# SCH_LED-bargraph-1_6_2024-11-01.net
KiCad netlist of a schematic drawn in EasyEDA
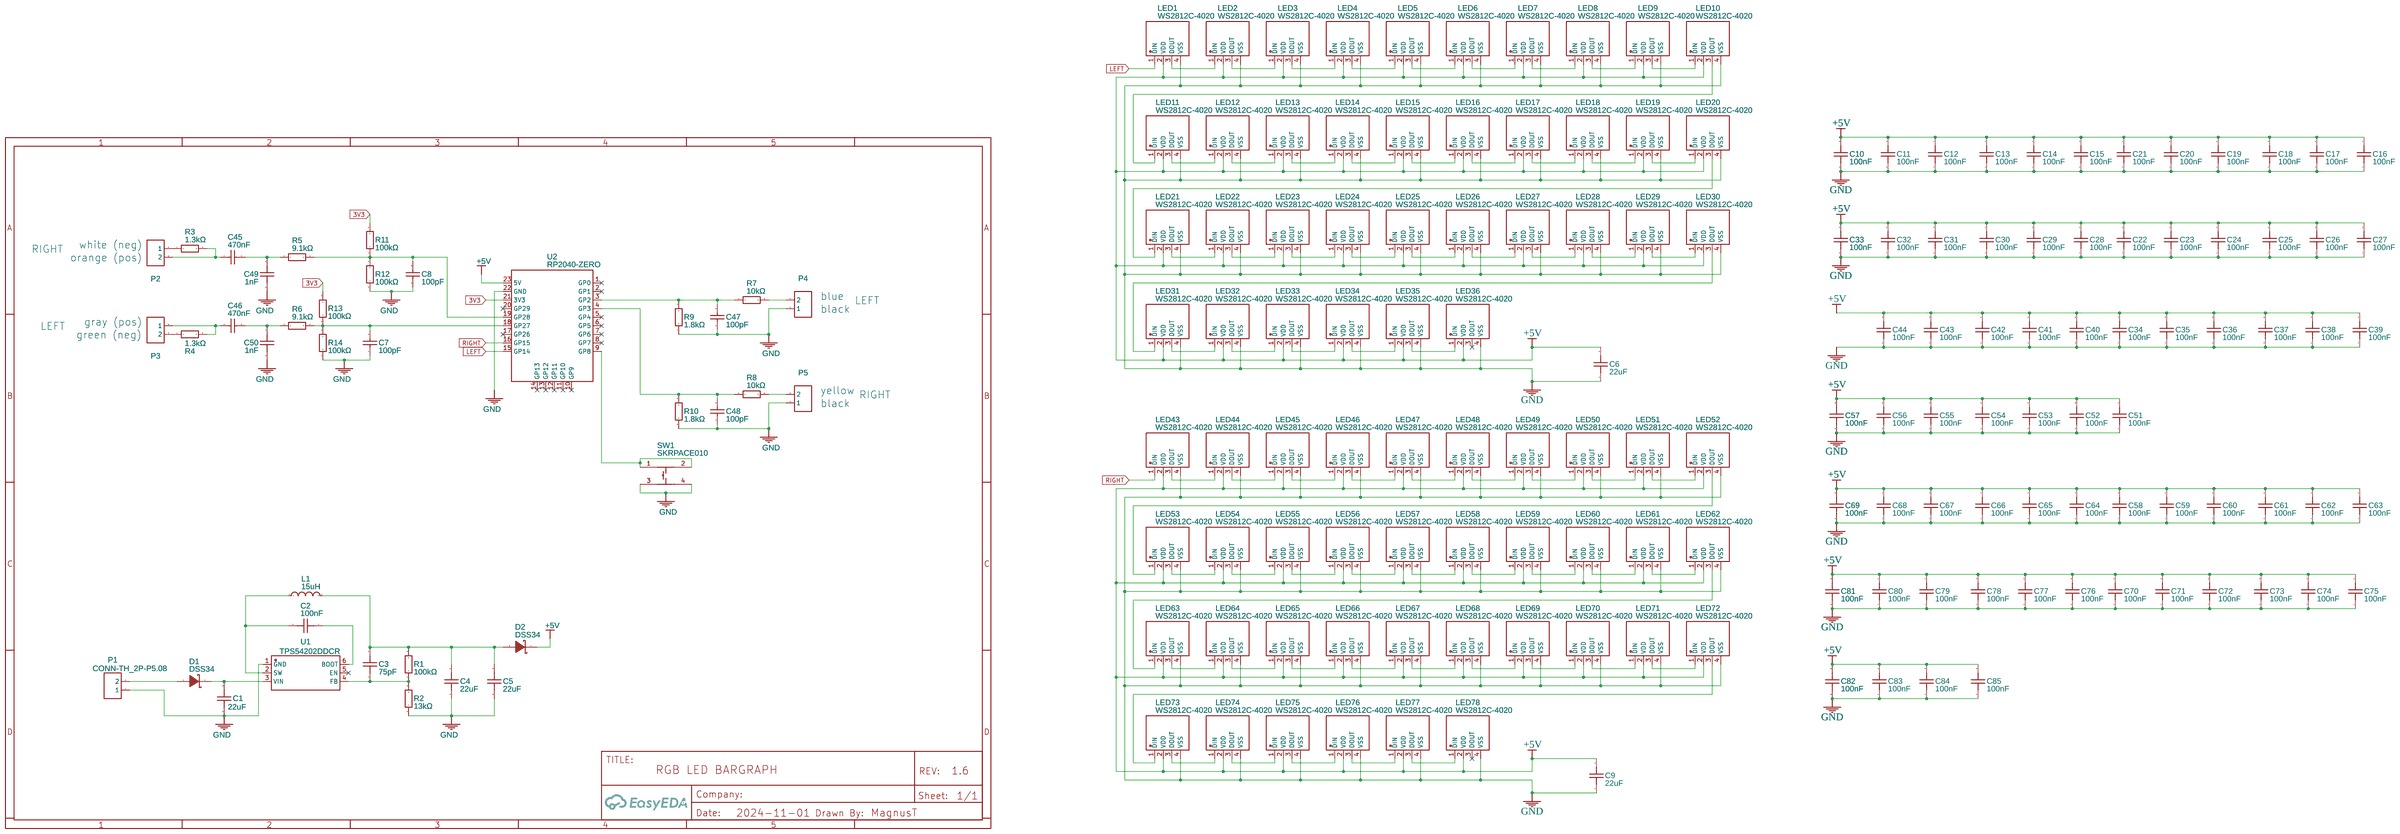
[diagram p0: schematic sheet]

(export (version "E")
  (design (tool "Eeschema 10.0.6"))
  (components
    (comp (ref "C1")
      (value "22uF")
      (fields
        (field (name "Manufacturer Part") "CL21A226MAYNNNE")
        (field (name "Manufacturer") "Samsung Electro-Mechanics")
      )
      (libsource (lib "") (part "CL21A226MAYNNNE"))
    )
    (comp (ref "C2")
      (value "100nF")
      (fields
        (field (name "Manufacturer Part") "CL05B104KO5NNNC")
        (field (name "Manufacturer") "SAMSUNG(三星)")
      )
      (libsource (lib "") (part "CL05B104KO5NNNC_1"))
    )
    (comp (ref "C3")
      (value "75pF")
      (fields
        (field (name "Manufacturer Part") "CC0603JRNPO9BN750")
        (field (name "Manufacturer") "YAGEO(国巨)")
      )
      (libsource (lib "") (part "CC0603JRNPO9BN750"))
    )
    (comp (ref "C4")
      (value "22uF")
      (fields (field (name "Manufacturer Part") "CL10A226MQ8NRNC") (field (name "Manufacturer") "SAMSUNG"))
      (libsource (lib "") (part "CL10A226MQ8NRNC"))
    )
    (comp (ref "C5")
      (value "22uF")
      (fields (field (name "Manufacturer Part") "CL10A226MQ8NRNC") (field (name "Manufacturer") "SAMSUNG"))
      (libsource (lib "") (part "CL10A226MQ8NRNC"))
    )
    (comp (ref "C6")
      (value "22uF")
      (fields (field (name "Manufacturer Part") "CL10A226MQ8NRNC") (field (name "Manufacturer") "SAMSUNG"))
      (libsource (lib "") (part "CL10A226MQ8NRNC"))
    )
    (comp (ref "C7")
      (value "100pF")
      (fields
        (field (name "Manufacturer Part") "CL10C101JB8NNNC")
        (field (name "Manufacturer") "SAMSUNG(三星)")
      )
      (libsource (lib "") (part "CL10C101JB8NNNC"))
    )
    (comp (ref "C8")
      (value "100pF")
      (fields
        (field (name "Manufacturer Part") "CL10C101JB8NNNC")
        (field (name "Manufacturer") "SAMSUNG(三星)")
      )
      (libsource (lib "") (part "CL10C101JB8NNNC"))
    )
    (comp (ref "C9")
      (value "22uF")
      (fields (field (name "Manufacturer Part") "CL10A226MQ8NRNC") (field (name "Manufacturer") "SAMSUNG"))
      (libsource (lib "") (part "CL10A226MQ8NRNC"))
    )
    (comp (ref "C10")
      (value "100nF")
      (fields
        (field (name "Manufacturer Part") "CL05B104KO5NNNC")
        (field (name "Manufacturer") "SAMSUNG(三星)")
      )
      (libsource (lib "") (part "CL05B104KO5NNNC"))
    )
    (comp (ref "C11")
      (value "100nF")
      (fields
        (field (name "Manufacturer Part") "CL05B104KO5NNNC")
        (field (name "Manufacturer") "SAMSUNG(三星)")
      )
      (libsource (lib "") (part "CL05B104KO5NNNC"))
    )
    (comp (ref "C12")
      (value "100nF")
      (fields
        (field (name "Manufacturer Part") "CL05B104KO5NNNC")
        (field (name "Manufacturer") "SAMSUNG(三星)")
      )
      (libsource (lib "") (part "CL05B104KO5NNNC"))
    )
    (comp (ref "C13")
      (value "100nF")
      (fields
        (field (name "Manufacturer Part") "CL05B104KO5NNNC")
        (field (name "Manufacturer") "SAMSUNG(三星)")
      )
      (libsource (lib "") (part "CL05B104KO5NNNC"))
    )
    (comp (ref "C14")
      (value "100nF")
      (fields
        (field (name "Manufacturer Part") "CL05B104KO5NNNC")
        (field (name "Manufacturer") "SAMSUNG(三星)")
      )
      (libsource (lib "") (part "CL05B104KO5NNNC"))
    )
    (comp (ref "C15")
      (value "100nF")
      (fields
        (field (name "Manufacturer Part") "CL05B104KO5NNNC")
        (field (name "Manufacturer") "SAMSUNG(三星)")
      )
      (libsource (lib "") (part "CL05B104KO5NNNC"))
    )
    (comp (ref "C16")
      (value "100nF")
      (fields
        (field (name "Manufacturer Part") "CL05B104KO5NNNC")
        (field (name "Manufacturer") "SAMSUNG(三星)")
      )
      (libsource (lib "") (part "CL05B104KO5NNNC"))
    )
    (comp (ref "C17")
      (value "100nF")
      (fields
        (field (name "Manufacturer Part") "CL05B104KO5NNNC")
        (field (name "Manufacturer") "SAMSUNG(三星)")
      )
      (libsource (lib "") (part "CL05B104KO5NNNC"))
    )
    (comp (ref "C18")
      (value "100nF")
      (fields
        (field (name "Manufacturer Part") "CL05B104KO5NNNC")
        (field (name "Manufacturer") "SAMSUNG(三星)")
      )
      (libsource (lib "") (part "CL05B104KO5NNNC"))
    )
    (comp (ref "C19")
      (value "100nF")
      (fields
        (field (name "Manufacturer Part") "CL05B104KO5NNNC")
        (field (name "Manufacturer") "SAMSUNG(三星)")
      )
      (libsource (lib "") (part "CL05B104KO5NNNC"))
    )
    (comp (ref "C20")
      (value "100nF")
      (fields
        (field (name "Manufacturer Part") "CL05B104KO5NNNC")
        (field (name "Manufacturer") "SAMSUNG(三星)")
      )
      (libsource (lib "") (part "CL05B104KO5NNNC"))
    )
    (comp (ref "C21")
      (value "100nF")
      (fields
        (field (name "Manufacturer Part") "CL05B104KO5NNNC")
        (field (name "Manufacturer") "SAMSUNG(三星)")
      )
      (libsource (lib "") (part "CL05B104KO5NNNC"))
    )
    (comp (ref "C22")
      (value "100nF")
      (fields
        (field (name "Manufacturer Part") "CL05B104KO5NNNC")
        (field (name "Manufacturer") "SAMSUNG(三星)")
      )
      (libsource (lib "") (part "CL05B104KO5NNNC"))
    )
    (comp (ref "C23")
      (value "100nF")
      (fields
        (field (name "Manufacturer Part") "CL05B104KO5NNNC")
        (field (name "Manufacturer") "SAMSUNG(三星)")
      )
      (libsource (lib "") (part "CL05B104KO5NNNC"))
    )
    (comp (ref "C24")
      (value "100nF")
      (fields
        (field (name "Manufacturer Part") "CL05B104KO5NNNC")
        (field (name "Manufacturer") "SAMSUNG(三星)")
      )
      (libsource (lib "") (part "CL05B104KO5NNNC"))
    )
    (comp (ref "C25")
      (value "100nF")
      (fields
        (field (name "Manufacturer Part") "CL05B104KO5NNNC")
        (field (name "Manufacturer") "SAMSUNG(三星)")
      )
      (libsource (lib "") (part "CL05B104KO5NNNC"))
    )
    (comp (ref "C26")
      (value "100nF")
      (fields
        (field (name "Manufacturer Part") "CL05B104KO5NNNC")
        (field (name "Manufacturer") "SAMSUNG(三星)")
      )
      (libsource (lib "") (part "CL05B104KO5NNNC"))
    )
    (comp (ref "C27")
      (value "100nF")
      (fields
        (field (name "Manufacturer Part") "CL05B104KO5NNNC")
        (field (name "Manufacturer") "SAMSUNG(三星)")
      )
      (libsource (lib "") (part "CL05B104KO5NNNC"))
    )
    (comp (ref "C28")
      (value "100nF")
      (fields
        (field (name "Manufacturer Part") "CL05B104KO5NNNC")
        (field (name "Manufacturer") "SAMSUNG(三星)")
      )
      (libsource (lib "") (part "CL05B104KO5NNNC"))
    )
    (comp (ref "C29")
      (value "100nF")
      (fields
        (field (name "Manufacturer Part") "CL05B104KO5NNNC")
        (field (name "Manufacturer") "SAMSUNG(三星)")
      )
      (libsource (lib "") (part "CL05B104KO5NNNC"))
    )
    (comp (ref "C30")
      (value "100nF")
      (fields
        (field (name "Manufacturer Part") "CL05B104KO5NNNC")
        (field (name "Manufacturer") "SAMSUNG(三星)")
      )
      (libsource (lib "") (part "CL05B104KO5NNNC"))
    )
    (comp (ref "C31")
      (value "100nF")
      (fields
        (field (name "Manufacturer Part") "CL05B104KO5NNNC")
        (field (name "Manufacturer") "SAMSUNG(三星)")
      )
      (libsource (lib "") (part "CL05B104KO5NNNC"))
    )
    (comp (ref "C32")
      (value "100nF")
      (fields
        (field (name "Manufacturer Part") "CL05B104KO5NNNC")
        (field (name "Manufacturer") "SAMSUNG(三星)")
      )
      (libsource (lib "") (part "CL05B104KO5NNNC"))
    )
    (comp (ref "C33")
      (value "100nF")
      (fields
        (field (name "Manufacturer Part") "CL05B104KO5NNNC")
        (field (name "Manufacturer") "SAMSUNG(三星)")
      )
      (libsource (lib "") (part "CL05B104KO5NNNC"))
    )
    (comp (ref "C34")
      (value "100nF")
      (fields
        (field (name "Manufacturer Part") "CL05B104KO5NNNC")
        (field (name "Manufacturer") "SAMSUNG(三星)")
      )
      (libsource (lib "") (part "CL05B104KO5NNNC"))
    )
    (comp (ref "C35")
      (value "100nF")
      (fields
        (field (name "Manufacturer Part") "CL05B104KO5NNNC")
        (field (name "Manufacturer") "SAMSUNG(三星)")
      )
      (libsource (lib "") (part "CL05B104KO5NNNC"))
    )
    (comp (ref "C36")
      (value "100nF")
      (fields
        (field (name "Manufacturer Part") "CL05B104KO5NNNC")
        (field (name "Manufacturer") "SAMSUNG(三星)")
      )
      (libsource (lib "") (part "CL05B104KO5NNNC"))
    )
    (comp (ref "C37")
      (value "100nF")
      (fields
        (field (name "Manufacturer Part") "CL05B104KO5NNNC")
        (field (name "Manufacturer") "SAMSUNG(三星)")
      )
      (libsource (lib "") (part "CL05B104KO5NNNC"))
    )
    (comp (ref "C38")
      (value "100nF")
      (fields
        (field (name "Manufacturer Part") "CL05B104KO5NNNC")
        (field (name "Manufacturer") "SAMSUNG(三星)")
      )
      (libsource (lib "") (part "CL05B104KO5NNNC"))
    )
    (comp (ref "C39")
      (value "100nF")
      (fields
        (field (name "Manufacturer Part") "CL05B104KO5NNNC")
        (field (name "Manufacturer") "SAMSUNG(三星)")
      )
      (libsource (lib "") (part "CL05B104KO5NNNC"))
    )
    (comp (ref "C40")
      (value "100nF")
      (fields
        (field (name "Manufacturer Part") "CL05B104KO5NNNC")
        (field (name "Manufacturer") "SAMSUNG(三星)")
      )
      (libsource (lib "") (part "CL05B104KO5NNNC"))
    )
    (comp (ref "C41")
      (value "100nF")
      (fields
        (field (name "Manufacturer Part") "CL05B104KO5NNNC")
        (field (name "Manufacturer") "SAMSUNG(三星)")
      )
      (libsource (lib "") (part "CL05B104KO5NNNC"))
    )
    (comp (ref "C42")
      (value "100nF")
      (fields
        (field (name "Manufacturer Part") "CL05B104KO5NNNC")
        (field (name "Manufacturer") "SAMSUNG(三星)")
      )
      (libsource (lib "") (part "CL05B104KO5NNNC"))
    )
    (comp (ref "C43")
      (value "100nF")
      (fields
        (field (name "Manufacturer Part") "CL05B104KO5NNNC")
        (field (name "Manufacturer") "SAMSUNG(三星)")
      )
      (libsource (lib "") (part "CL05B104KO5NNNC"))
    )
    (comp (ref "C44")
      (value "100nF")
      (fields
        (field (name "Manufacturer Part") "CL05B104KO5NNNC")
        (field (name "Manufacturer") "SAMSUNG(三星)")
      )
      (libsource (lib "") (part "CL05B104KO5NNNC"))
    )
    (comp (ref "C45")
      (value "470nF")
      (fields
        (field (name "Manufacturer Part") "CL21B474KBFNNNE")
        (field (name "Manufacturer") "SAMSUNG(三星)")
      )
      (libsource (lib "") (part "CL21B474KBFNNNE"))
    )
    (comp (ref "C46")
      (value "470nF")
      (fields
        (field (name "Manufacturer Part") "CL21B474KBFNNNE")
        (field (name "Manufacturer") "SAMSUNG(三星)")
      )
      (libsource (lib "") (part "CL21B474KBFNNNE"))
    )
    (comp (ref "C47")
      (value "100pF")
      (fields
        (field (name "Manufacturer Part") "CL10C101JB8NNNC")
        (field (name "Manufacturer") "SAMSUNG(三星)")
      )
      (libsource (lib "") (part "CL10C101JB8NNNC"))
    )
    (comp (ref "C48")
      (value "100pF")
      (fields
        (field (name "Manufacturer Part") "CL10C101JB8NNNC")
        (field (name "Manufacturer") "SAMSUNG(三星)")
      )
      (libsource (lib "") (part "CL10C101JB8NNNC"))
    )
    (comp (ref "C49")
      (value "1nF")
      (fields
        (field (name "Manufacturer Part") "CL10C102JB8NNNC")
        (field (name "Manufacturer") "SAMSUNG(三星)")
      )
      (libsource (lib "") (part "CL10C102JB8NNNC"))
    )
    (comp (ref "C50")
      (value "1nF")
      (fields
        (field (name "Manufacturer Part") "CL10C102JB8NNNC")
        (field (name "Manufacturer") "SAMSUNG(三星)")
      )
      (libsource (lib "") (part "CL10C102JB8NNNC"))
    )
    (comp (ref "C51")
      (value "100nF")
      (fields
        (field (name "Manufacturer Part") "CL05B104KO5NNNC")
        (field (name "Manufacturer") "SAMSUNG(三星)")
      )
      (libsource (lib "") (part "CL05B104KO5NNNC"))
    )
    (comp (ref "C52")
      (value "100nF")
      (fields
        (field (name "Manufacturer Part") "CL05B104KO5NNNC")
        (field (name "Manufacturer") "SAMSUNG(三星)")
      )
      (libsource (lib "") (part "CL05B104KO5NNNC"))
    )
    (comp (ref "C53")
      (value "100nF")
      (fields
        (field (name "Manufacturer Part") "CL05B104KO5NNNC")
        (field (name "Manufacturer") "SAMSUNG(三星)")
      )
      (libsource (lib "") (part "CL05B104KO5NNNC"))
    )
    (comp (ref "C54")
      (value "100nF")
      (fields
        (field (name "Manufacturer Part") "CL05B104KO5NNNC")
        (field (name "Manufacturer") "SAMSUNG(三星)")
      )
      (libsource (lib "") (part "CL05B104KO5NNNC"))
    )
    (comp (ref "C55")
      (value "100nF")
      (fields
        (field (name "Manufacturer Part") "CL05B104KO5NNNC")
        (field (name "Manufacturer") "SAMSUNG(三星)")
      )
      (libsource (lib "") (part "CL05B104KO5NNNC"))
    )
    (comp (ref "C56")
      (value "100nF")
      (fields
        (field (name "Manufacturer Part") "CL05B104KO5NNNC")
        (field (name "Manufacturer") "SAMSUNG(三星)")
      )
      (libsource (lib "") (part "CL05B104KO5NNNC"))
    )
    (comp (ref "C57")
      (value "100nF")
      (fields
        (field (name "Manufacturer Part") "CL05B104KO5NNNC")
        (field (name "Manufacturer") "SAMSUNG(三星)")
      )
      (libsource (lib "") (part "CL05B104KO5NNNC"))
    )
    (comp (ref "C58")
      (value "100nF")
      (fields
        (field (name "Manufacturer Part") "CL05B104KO5NNNC")
        (field (name "Manufacturer") "SAMSUNG(三星)")
      )
      (libsource (lib "") (part "CL05B104KO5NNNC"))
    )
    (comp (ref "C59")
      (value "100nF")
      (fields
        (field (name "Manufacturer Part") "CL05B104KO5NNNC")
        (field (name "Manufacturer") "SAMSUNG(三星)")
      )
      (libsource (lib "") (part "CL05B104KO5NNNC"))
    )
    (comp (ref "C60")
      (value "100nF")
      (fields
        (field (name "Manufacturer Part") "CL05B104KO5NNNC")
        (field (name "Manufacturer") "SAMSUNG(三星)")
      )
      (libsource (lib "") (part "CL05B104KO5NNNC"))
    )
    (comp (ref "C61")
      (value "100nF")
      (fields
        (field (name "Manufacturer Part") "CL05B104KO5NNNC")
        (field (name "Manufacturer") "SAMSUNG(三星)")
      )
      (libsource (lib "") (part "CL05B104KO5NNNC"))
    )
    (comp (ref "C62")
      (value "100nF")
      (fields
        (field (name "Manufacturer Part") "CL05B104KO5NNNC")
        (field (name "Manufacturer") "SAMSUNG(三星)")
      )
      (libsource (lib "") (part "CL05B104KO5NNNC"))
    )
    (comp (ref "C63")
      (value "100nF")
      (fields
        (field (name "Manufacturer Part") "CL05B104KO5NNNC")
        (field (name "Manufacturer") "SAMSUNG(三星)")
      )
      (libsource (lib "") (part "CL05B104KO5NNNC"))
    )
    (comp (ref "C64")
      (value "100nF")
      (fields
        (field (name "Manufacturer Part") "CL05B104KO5NNNC")
        (field (name "Manufacturer") "SAMSUNG(三星)")
      )
      (libsource (lib "") (part "CL05B104KO5NNNC"))
    )
    (comp (ref "C65")
      (value "100nF")
      (fields
        (field (name "Manufacturer Part") "CL05B104KO5NNNC")
        (field (name "Manufacturer") "SAMSUNG(三星)")
      )
      (libsource (lib "") (part "CL05B104KO5NNNC"))
    )
    (comp (ref "C66")
      (value "100nF")
      (fields
        (field (name "Manufacturer Part") "CL05B104KO5NNNC")
        (field (name "Manufacturer") "SAMSUNG(三星)")
      )
      (libsource (lib "") (part "CL05B104KO5NNNC"))
    )
    (comp (ref "C67")
      (value "100nF")
      (fields
        (field (name "Manufacturer Part") "CL05B104KO5NNNC")
        (field (name "Manufacturer") "SAMSUNG(三星)")
      )
      (libsource (lib "") (part "CL05B104KO5NNNC"))
    )
    (comp (ref "C68")
      (value "100nF")
      (fields
        (field (name "Manufacturer Part") "CL05B104KO5NNNC")
        (field (name "Manufacturer") "SAMSUNG(三星)")
      )
      (libsource (lib "") (part "CL05B104KO5NNNC"))
    )
    (comp (ref "C69")
      (value "100nF")
      (fields
        (field (name "Manufacturer Part") "CL05B104KO5NNNC")
        (field (name "Manufacturer") "SAMSUNG(三星)")
      )
      (libsource (lib "") (part "CL05B104KO5NNNC"))
    )
    (comp (ref "C70")
      (value "100nF")
      (fields
        (field (name "Manufacturer Part") "CL05B104KO5NNNC")
        (field (name "Manufacturer") "SAMSUNG(三星)")
      )
      (libsource (lib "") (part "CL05B104KO5NNNC"))
    )
    (comp (ref "C71")
      (value "100nF")
      (fields
        (field (name "Manufacturer Part") "CL05B104KO5NNNC")
        (field (name "Manufacturer") "SAMSUNG(三星)")
      )
      (libsource (lib "") (part "CL05B104KO5NNNC"))
    )
    (comp (ref "C72")
      (value "100nF")
      (fields
        (field (name "Manufacturer Part") "CL05B104KO5NNNC")
        (field (name "Manufacturer") "SAMSUNG(三星)")
      )
      (libsource (lib "") (part "CL05B104KO5NNNC"))
    )
    (comp (ref "C73")
      (value "100nF")
      (fields
        (field (name "Manufacturer Part") "CL05B104KO5NNNC")
        (field (name "Manufacturer") "SAMSUNG(三星)")
      )
      (libsource (lib "") (part "CL05B104KO5NNNC"))
    )
    (comp (ref "C74")
      (value "100nF")
      (fields
        (field (name "Manufacturer Part") "CL05B104KO5NNNC")
        (field (name "Manufacturer") "SAMSUNG(三星)")
      )
      (libsource (lib "") (part "CL05B104KO5NNNC"))
    )
    (comp (ref "C75")
      (value "100nF")
      (fields
        (field (name "Manufacturer Part") "CL05B104KO5NNNC")
        (field (name "Manufacturer") "SAMSUNG(三星)")
      )
      (libsource (lib "") (part "CL05B104KO5NNNC"))
    )
    (comp (ref "C76")
      (value "100nF")
      (fields
        (field (name "Manufacturer Part") "CL05B104KO5NNNC")
        (field (name "Manufacturer") "SAMSUNG(三星)")
      )
      (libsource (lib "") (part "CL05B104KO5NNNC"))
    )
    (comp (ref "C77")
      (value "100nF")
      (fields
        (field (name "Manufacturer Part") "CL05B104KO5NNNC")
        (field (name "Manufacturer") "SAMSUNG(三星)")
      )
      (libsource (lib "") (part "CL05B104KO5NNNC"))
    )
    (comp (ref "C78")
      (value "100nF")
      (fields
        (field (name "Manufacturer Part") "CL05B104KO5NNNC")
        (field (name "Manufacturer") "SAMSUNG(三星)")
      )
      (libsource (lib "") (part "CL05B104KO5NNNC"))
    )
    (comp (ref "C79")
      (value "100nF")
      (fields
        (field (name "Manufacturer Part") "CL05B104KO5NNNC")
        (field (name "Manufacturer") "SAMSUNG(三星)")
      )
      (libsource (lib "") (part "CL05B104KO5NNNC"))
    )
    (comp (ref "C80")
      (value "100nF")
      (fields
        (field (name "Manufacturer Part") "CL05B104KO5NNNC")
        (field (name "Manufacturer") "SAMSUNG(三星)")
      )
      (libsource (lib "") (part "CL05B104KO5NNNC"))
    )
    (comp (ref "C81")
      (value "100nF")
      (fields
        (field (name "Manufacturer Part") "CL05B104KO5NNNC")
        (field (name "Manufacturer") "SAMSUNG(三星)")
      )
      (libsource (lib "") (part "CL05B104KO5NNNC"))
    )
    (comp (ref "C82")
      (value "100nF")
      (fields
        (field (name "Manufacturer Part") "CL05B104KO5NNNC")
        (field (name "Manufacturer") "SAMSUNG(三星)")
      )
      (libsource (lib "") (part "CL05B104KO5NNNC"))
    )
    (comp (ref "C83")
      (value "100nF")
      (fields
        (field (name "Manufacturer Part") "CL05B104KO5NNNC")
        (field (name "Manufacturer") "SAMSUNG(三星)")
      )
      (libsource (lib "") (part "CL05B104KO5NNNC"))
    )
    (comp (ref "C84")
      (value "100nF")
      (fields
        (field (name "Manufacturer Part") "CL05B104KO5NNNC")
        (field (name "Manufacturer") "SAMSUNG(三星)")
      )
      (libsource (lib "") (part "CL05B104KO5NNNC"))
    )
    (comp (ref "C85")
      (value "100nF")
      (fields
        (field (name "Manufacturer Part") "CL05B104KO5NNNC")
        (field (name "Manufacturer") "SAMSUNG(三星)")
      )
      (libsource (lib "") (part "CL05B104KO5NNNC"))
    )
    (comp (ref "D1")
      (value "DSS34")
      (fields (field (name "Manufacturer") "STARSEA"))
      (libsource (lib "") (part "DSS34"))
    )
    (comp (ref "D2")
      (value "DSS34")
      (fields (field (name "Manufacturer") "STARSEA"))
      (libsource (lib "") (part "DSS34"))
    )
    (comp (ref "L1")
      (value "15uH")
      (fields
        (field (name "Manufacturer Part") "SLP6028S150MTT")
        (field (name "Manufacturer") "Sunltech(韩国顺磁)")
      )
      (libsource (lib "") (part "SLP6028S150MTT"))
    )
    (comp (ref "LED1")
      (value "WS2812C-4020")
      (fields (field (name "Manufacturer") "worldsemi"))
      (libsource (lib "") (part "WS2812C-4020"))
    )
    (comp (ref "LED2")
      (value "WS2812C-4020")
      (fields (field (name "Manufacturer") "worldsemi"))
      (libsource (lib "") (part "WS2812C-4020"))
    )
    (comp (ref "LED3")
      (value "WS2812C-4020")
      (fields (field (name "Manufacturer") "worldsemi"))
      (libsource (lib "") (part "WS2812C-4020"))
    )
    (comp (ref "LED4")
      (value "WS2812C-4020")
      (fields (field (name "Manufacturer") "worldsemi"))
      (libsource (lib "") (part "WS2812C-4020"))
    )
    (comp (ref "LED5")
      (value "WS2812C-4020")
      (fields (field (name "Manufacturer") "worldsemi"))
      (libsource (lib "") (part "WS2812C-4020"))
    )
    (comp (ref "LED6")
      (value "WS2812C-4020")
      (fields (field (name "Manufacturer") "worldsemi"))
      (libsource (lib "") (part "WS2812C-4020"))
    )
    (comp (ref "LED7")
      (value "WS2812C-4020")
      (fields (field (name "Manufacturer") "worldsemi"))
      (libsource (lib "") (part "WS2812C-4020"))
    )
    (comp (ref "LED8")
      (value "WS2812C-4020")
      (fields (field (name "Manufacturer") "worldsemi"))
      (libsource (lib "") (part "WS2812C-4020"))
    )
    (comp (ref "LED9")
      (value "WS2812C-4020")
      (fields (field (name "Manufacturer") "worldsemi"))
      (libsource (lib "") (part "WS2812C-4020"))
    )
    (comp (ref "LED10")
      (value "WS2812C-4020")
      (fields (field (name "Manufacturer") "worldsemi"))
      (libsource (lib "") (part "WS2812C-4020"))
    )
    (comp (ref "LED11")
      (value "WS2812C-4020")
      (fields (field (name "Manufacturer") "worldsemi"))
      (libsource (lib "") (part "WS2812C-4020"))
    )
    (comp (ref "LED12")
      (value "WS2812C-4020")
      (fields (field (name "Manufacturer") "worldsemi"))
      (libsource (lib "") (part "WS2812C-4020"))
    )
    (comp (ref "LED13")
      (value "WS2812C-4020")
      (fields (field (name "Manufacturer") "worldsemi"))
      (libsource (lib "") (part "WS2812C-4020"))
    )
    (comp (ref "LED14")
      (value "WS2812C-4020")
      (fields (field (name "Manufacturer") "worldsemi"))
      (libsource (lib "") (part "WS2812C-4020"))
    )
    (comp (ref "LED15")
      (value "WS2812C-4020")
      (fields (field (name "Manufacturer") "worldsemi"))
      (libsource (lib "") (part "WS2812C-4020"))
    )
    (comp (ref "LED16")
      (value "WS2812C-4020")
      (fields (field (name "Manufacturer") "worldsemi"))
      (libsource (lib "") (part "WS2812C-4020"))
    )
    (comp (ref "LED17")
      (value "WS2812C-4020")
      (fields (field (name "Manufacturer") "worldsemi"))
      (libsource (lib "") (part "WS2812C-4020"))
    )
    (comp (ref "LED18")
      (value "WS2812C-4020")
      (fields (field (name "Manufacturer") "worldsemi"))
      (libsource (lib "") (part "WS2812C-4020"))
    )
    (comp (ref "LED19")
      (value "WS2812C-4020")
      (fields (field (name "Manufacturer") "worldsemi"))
      (libsource (lib "") (part "WS2812C-4020"))
    )
    (comp (ref "LED20")
      (value "WS2812C-4020")
      (fields (field (name "Manufacturer") "worldsemi"))
      (libsource (lib "") (part "WS2812C-4020"))
    )
    (comp (ref "LED21")
      (value "WS2812C-4020")
      (fields (field (name "Manufacturer") "worldsemi"))
      (libsource (lib "") (part "WS2812C-4020"))
    )
    (comp (ref "LED22")
      (value "WS2812C-4020")
      (fields (field (name "Manufacturer") "worldsemi"))
      (libsource (lib "") (part "WS2812C-4020"))
    )
    (comp (ref "LED23")
      (value "WS2812C-4020")
      (fields (field (name "Manufacturer") "worldsemi"))
      (libsource (lib "") (part "WS2812C-4020"))
    )
    (comp (ref "LED24")
      (value "WS2812C-4020")
      (fields (field (name "Manufacturer") "worldsemi"))
      (libsource (lib "") (part "WS2812C-4020"))
    )
    (comp (ref "LED25")
      (value "WS2812C-4020")
      (fields (field (name "Manufacturer") "worldsemi"))
      (libsource (lib "") (part "WS2812C-4020"))
    )
    (comp (ref "LED26")
      (value "WS2812C-4020")
      (fields (field (name "Manufacturer") "worldsemi"))
      (libsource (lib "") (part "WS2812C-4020"))
    )
    (comp (ref "LED27")
      (value "WS2812C-4020")
      (fields (field (name "Manufacturer") "worldsemi"))
      (libsource (lib "") (part "WS2812C-4020"))
    )
    (comp (ref "LED28")
      (value "WS2812C-4020")
      (fields (field (name "Manufacturer") "worldsemi"))
      (libsource (lib "") (part "WS2812C-4020"))
    )
    (comp (ref "LED29")
      (value "WS2812C-4020")
      (fields (field (name "Manufacturer") "worldsemi"))
      (libsource (lib "") (part "WS2812C-4020"))
    )
    (comp (ref "LED30")
      (value "WS2812C-4020")
      (fields (field (name "Manufacturer") "worldsemi"))
      (libsource (lib "") (part "WS2812C-4020"))
    )
    (comp (ref "LED31")
      (value "WS2812C-4020")
      (fields (field (name "Manufacturer") "worldsemi"))
      (libsource (lib "") (part "WS2812C-4020"))
    )
    (comp (ref "LED32")
      (value "WS2812C-4020")
      (fields (field (name "Manufacturer") "worldsemi"))
      (libsource (lib "") (part "WS2812C-4020"))
    )
    (comp (ref "LED33")
      (value "WS2812C-4020")
      (fields (field (name "Manufacturer") "worldsemi"))
      (libsource (lib "") (part "WS2812C-4020"))
    )
    (comp (ref "LED34")
      (value "WS2812C-4020")
      (fields (field (name "Manufacturer") "worldsemi"))
      (libsource (lib "") (part "WS2812C-4020"))
    )
    (comp (ref "LED35")
      (value "WS2812C-4020")
      (fields (field (name "Manufacturer") "worldsemi"))
      (libsource (lib "") (part "WS2812C-4020"))
    )
    (comp (ref "LED36")
      (value "WS2812C-4020")
      (fields (field (name "Manufacturer") "worldsemi"))
      (libsource (lib "") (part "WS2812C-4020"))
    )
    (comp (ref "LED43")
      (value "WS2812C-4020")
      (fields (field (name "Manufacturer") "worldsemi"))
      (libsource (lib "") (part "WS2812C-4020"))
    )
    (comp (ref "LED44")
      (value "WS2812C-4020")
      (fields (field (name "Manufacturer") "worldsemi"))
      (libsource (lib "") (part "WS2812C-4020"))
    )
    (comp (ref "LED45")
      (value "WS2812C-4020")
      (fields (field (name "Manufacturer") "worldsemi"))
      (libsource (lib "") (part "WS2812C-4020"))
    )
    (comp (ref "LED46")
      (value "WS2812C-4020")
      (fields (field (name "Manufacturer") "worldsemi"))
      (libsource (lib "") (part "WS2812C-4020"))
    )
    (comp (ref "LED47")
      (value "WS2812C-4020")
      (fields (field (name "Manufacturer") "worldsemi"))
      (libsource (lib "") (part "WS2812C-4020"))
    )
    (comp (ref "LED48")
      (value "WS2812C-4020")
      (fields (field (name "Manufacturer") "worldsemi"))
      (libsource (lib "") (part "WS2812C-4020"))
    )
    (comp (ref "LED49")
      (value "WS2812C-4020")
      (fields (field (name "Manufacturer") "worldsemi"))
      (libsource (lib "") (part "WS2812C-4020"))
    )
    (comp (ref "LED50")
      (value "WS2812C-4020")
      (fields (field (name "Manufacturer") "worldsemi"))
      (libsource (lib "") (part "WS2812C-4020"))
    )
    (comp (ref "LED51")
      (value "WS2812C-4020")
      (fields (field (name "Manufacturer") "worldsemi"))
      (libsource (lib "") (part "WS2812C-4020"))
    )
    (comp (ref "LED52")
      (value "WS2812C-4020")
      (fields (field (name "Manufacturer") "worldsemi"))
      (libsource (lib "") (part "WS2812C-4020"))
    )
    (comp (ref "LED53")
      (value "WS2812C-4020")
      (fields (field (name "Manufacturer") "worldsemi"))
      (libsource (lib "") (part "WS2812C-4020"))
    )
    (comp (ref "LED54")
      (value "WS2812C-4020")
      (fields (field (name "Manufacturer") "worldsemi"))
      (libsource (lib "") (part "WS2812C-4020"))
    )
    (comp (ref "LED55")
      (value "WS2812C-4020")
      (fields (field (name "Manufacturer") "worldsemi"))
      (libsource (lib "") (part "WS2812C-4020"))
    )
    (comp (ref "LED56")
      (value "WS2812C-4020")
      (fields (field (name "Manufacturer") "worldsemi"))
      (libsource (lib "") (part "WS2812C-4020"))
    )
    (comp (ref "LED57")
      (value "WS2812C-4020")
      (fields (field (name "Manufacturer") "worldsemi"))
      (libsource (lib "") (part "WS2812C-4020"))
    )
    (comp (ref "LED58")
      (value "WS2812C-4020")
      (fields (field (name "Manufacturer") "worldsemi"))
      (libsource (lib "") (part "WS2812C-4020"))
    )
    (comp (ref "LED59")
      (value "WS2812C-4020")
      (fields (field (name "Manufacturer") "worldsemi"))
      (libsource (lib "") (part "WS2812C-4020"))
    )
    (comp (ref "LED60")
      (value "WS2812C-4020")
      (fields (field (name "Manufacturer") "worldsemi"))
      (libsource (lib "") (part "WS2812C-4020"))
    )
    (comp (ref "LED61")
      (value "WS2812C-4020")
      (fields (field (name "Manufacturer") "worldsemi"))
      (libsource (lib "") (part "WS2812C-4020"))
    )
    (comp (ref "LED62")
      (value "WS2812C-4020")
      (fields (field (name "Manufacturer") "worldsemi"))
      (libsource (lib "") (part "WS2812C-4020"))
    )
    (comp (ref "LED63")
      (value "WS2812C-4020")
      (fields (field (name "Manufacturer") "worldsemi"))
      (libsource (lib "") (part "WS2812C-4020"))
    )
    (comp (ref "LED64")
      (value "WS2812C-4020")
      (fields (field (name "Manufacturer") "worldsemi"))
      (libsource (lib "") (part "WS2812C-4020"))
    )
    (comp (ref "LED65")
      (value "WS2812C-4020")
      (fields (field (name "Manufacturer") "worldsemi"))
      (libsource (lib "") (part "WS2812C-4020"))
    )
    (comp (ref "LED66")
      (value "WS2812C-4020")
      (fields (field (name "Manufacturer") "worldsemi"))
      (libsource (lib "") (part "WS2812C-4020"))
    )
    (comp (ref "LED67")
      (value "WS2812C-4020")
      (fields (field (name "Manufacturer") "worldsemi"))
      (libsource (lib "") (part "WS2812C-4020"))
    )
    (comp (ref "LED68")
      (value "WS2812C-4020")
      (fields (field (name "Manufacturer") "worldsemi"))
      (libsource (lib "") (part "WS2812C-4020"))
    )
    (comp (ref "LED69")
      (value "WS2812C-4020")
      (fields (field (name "Manufacturer") "worldsemi"))
      (libsource (lib "") (part "WS2812C-4020"))
    )
    (comp (ref "LED70")
      (value "WS2812C-4020")
      (fields (field (name "Manufacturer") "worldsemi"))
      (libsource (lib "") (part "WS2812C-4020"))
    )
    (comp (ref "LED71")
      (value "WS2812C-4020")
      (fields (field (name "Manufacturer") "worldsemi"))
      (libsource (lib "") (part "WS2812C-4020"))
    )
    (comp (ref "LED72")
      (value "WS2812C-4020")
      (fields (field (name "Manufacturer") "worldsemi"))
      (libsource (lib "") (part "WS2812C-4020"))
    )
    (comp (ref "LED73")
      (value "WS2812C-4020")
      (fields (field (name "Manufacturer") "worldsemi"))
      (libsource (lib "") (part "WS2812C-4020"))
    )
    (comp (ref "LED74")
      (value "WS2812C-4020")
      (fields (field (name "Manufacturer") "worldsemi"))
      (libsource (lib "") (part "WS2812C-4020"))
    )
    (comp (ref "LED75")
      (value "WS2812C-4020")
      (fields (field (name "Manufacturer") "worldsemi"))
      (libsource (lib "") (part "WS2812C-4020"))
    )
    (comp (ref "LED76")
      (value "WS2812C-4020")
      (fields (field (name "Manufacturer") "worldsemi"))
      (libsource (lib "") (part "WS2812C-4020"))
    )
    (comp (ref "LED77")
      (value "WS2812C-4020")
      (fields (field (name "Manufacturer") "worldsemi"))
      (libsource (lib "") (part "WS2812C-4020"))
    )
    (comp (ref "LED78")
      (value "WS2812C-4020")
      (fields (field (name "Manufacturer") "worldsemi"))
      (libsource (lib "") (part "WS2812C-4020"))
    )
    (comp (ref "P1") (value "CONN-TH_2P-P5.08") (libsource (lib "") (part "CONN-TH_2P-P5.08")))
    (comp (ref "P2") (value "CONN-TH_2P-P5.08") (libsource (lib "") (part "CONN-TH_2P-P5.08_2")))
    (comp (ref "P3") (value "CONN-TH_2P-P5.08") (libsource (lib "") (part "CONN-TH_2P-P5.08_2")))
    (comp (ref "P4") (value "CONN-TH_2P-P5.08") (libsource (lib "") (part "CONN-TH_2P-P5.08_1")))
    (comp (ref "P5") (value "CONN-TH_2P-P5.08") (libsource (lib "") (part "CONN-TH_2P-P5.08_1")))
    (comp (ref "R1")
      (value "100kΩ")
      (fields
        (field (name "Manufacturer Part") "0603WAF1003T5E")
        (field (name "Manufacturer") "UNI-ROYAL(厚声)")
      )
      (libsource (lib "") (part "0603WAF1003T5E"))
    )
    (comp (ref "R2")
      (value "13kΩ")
      (fields
        (field (name "Manufacturer Part") "0603WAF1302T5E")
        (field (name "Manufacturer") "UNI-ROYAL(厚声)")
      )
      (libsource (lib "") (part "0603WAF1302T5E"))
    )
    (comp (ref "R3")
      (value "1.3kΩ")
      (fields
        (field (name "Manufacturer Part") "0603WAF1301T5E")
        (field (name "Manufacturer") "UNI-ROYAL(厚声)")
      )
      (libsource (lib "") (part "0603WAF1301T5E"))
    )
    (comp (ref "R4")
      (value "1.3kΩ")
      (fields
        (field (name "Manufacturer Part") "0603WAF1301T5E")
        (field (name "Manufacturer") "UNI-ROYAL(厚声)")
      )
      (libsource (lib "") (part "0603WAF1301T5E"))
    )
    (comp (ref "R5")
      (value "9.1kΩ")
      (fields
        (field (name "Manufacturer Part") "0603WAF9101T5E")
        (field (name "Manufacturer") "UNI-ROYAL(厚声)")
      )
      (libsource (lib "") (part "0603WAF9101T5E"))
    )
    (comp (ref "R6")
      (value "9.1kΩ")
      (fields
        (field (name "Manufacturer Part") "0603WAF9101T5E")
        (field (name "Manufacturer") "UNI-ROYAL(厚声)")
      )
      (libsource (lib "") (part "0603WAF9101T5E"))
    )
    (comp (ref "R7")
      (value "10kΩ")
      (fields
        (field (name "Manufacturer Part") "0603WAF1002T5E")
        (field (name "Manufacturer") "UNI-ROYAL(厚声)")
      )
      (libsource (lib "") (part "0603WAF1002T5E"))
    )
    (comp (ref "R8")
      (value "10kΩ")
      (fields
        (field (name "Manufacturer Part") "0603WAF1002T5E")
        (field (name "Manufacturer") "UNI-ROYAL(厚声)")
      )
      (libsource (lib "") (part "0603WAF1002T5E"))
    )
    (comp (ref "R9")
      (value "1.8kΩ")
      (fields
        (field (name "Manufacturer Part") "0603WAF1801T5E")
        (field (name "Manufacturer") "UNI-ROYAL(厚声)")
      )
      (libsource (lib "") (part "0603WAF1801T5E"))
    )
    (comp (ref "R10")
      (value "1.8kΩ")
      (fields
        (field (name "Manufacturer Part") "0603WAF1801T5E")
        (field (name "Manufacturer") "UNI-ROYAL(厚声)")
      )
      (libsource (lib "") (part "0603WAF1801T5E"))
    )
    (comp (ref "R11")
      (value "100kΩ")
      (fields
        (field (name "Manufacturer Part") "0603WAF1003T5E")
        (field (name "Manufacturer") "UNI-ROYAL(厚声)")
      )
      (libsource (lib "") (part "0603WAF1003T5E"))
    )
    (comp (ref "R12")
      (value "100kΩ")
      (fields
        (field (name "Manufacturer Part") "0603WAF1003T5E")
        (field (name "Manufacturer") "UNI-ROYAL(厚声)")
      )
      (libsource (lib "") (part "0603WAF1003T5E"))
    )
    (comp (ref "R13")
      (value "100kΩ")
      (fields
        (field (name "Manufacturer Part") "0603WAF1003T5E")
        (field (name "Manufacturer") "UNI-ROYAL(厚声)")
      )
      (libsource (lib "") (part "0603WAF1003T5E"))
    )
    (comp (ref "R14")
      (value "100kΩ")
      (fields
        (field (name "Manufacturer Part") "0603WAF1003T5E")
        (field (name "Manufacturer") "UNI-ROYAL(厚声)")
      )
      (libsource (lib "") (part "0603WAF1003T5E"))
    )
    (comp (ref "SW1")
      (value "SKRPACE010")
      (fields (field (name "Manufacturer") "ALPSALPINE(阿尔卑斯阿尔派)"))
      (libsource (lib "") (part "SKRPACE010"))
    )
    (comp (ref "U1")
      (value "TPS54202DDCR")
      (fields (field (name "Manufacturer") "TI(德州仪器)"))
      (libsource (lib "") (part "TPS54202DDCR"))
    )
    (comp (ref "U2")
      (value "RP2040-ZERO")
      (fields
        (field (name "Manufacturer Part") "RP2040-Zero")
        (field (name "Manufacturer") "Waveshare(微雪电子)")
      )
      (libsource (lib "") (part "RP2040-ZERO"))
    )
  )
  (nets
    (net (code "1") (name "+5V") (class "Default")
      (node (ref "C10") (pin "2") (pinfunction "2_2") (pintype "unspecified"))
      (node (ref "C11") (pin "2") (pinfunction "2_2") (pintype "unspecified"))
      (node (ref "C12") (pin "2") (pinfunction "2_2") (pintype "unspecified"))
      (node (ref "C13") (pin "2") (pinfunction "2_2") (pintype "unspecified"))
      (node (ref "C14") (pin "2") (pinfunction "2_2") (pintype "unspecified"))
      (node (ref "C15") (pin "2") (pinfunction "2_2") (pintype "unspecified"))
      (node (ref "C16") (pin "2") (pinfunction "2_2") (pintype "unspecified"))
      (node (ref "C17") (pin "2") (pinfunction "2_2") (pintype "unspecified"))
      (node (ref "C18") (pin "2") (pinfunction "2_2") (pintype "unspecified"))
      (node (ref "C19") (pin "2") (pinfunction "2_2") (pintype "unspecified"))
      (node (ref "C20") (pin "2") (pinfunction "2_2") (pintype "unspecified"))
      (node (ref "C21") (pin "2") (pinfunction "2_2") (pintype "unspecified"))
      (node (ref "C22") (pin "2") (pinfunction "2_2") (pintype "unspecified"))
      (node (ref "C23") (pin "2") (pinfunction "2_2") (pintype "unspecified"))
      (node (ref "C24") (pin "2") (pinfunction "2_2") (pintype "unspecified"))
      (node (ref "C25") (pin "2") (pinfunction "2_2") (pintype "unspecified"))
      (node (ref "C26") (pin "2") (pinfunction "2_2") (pintype "unspecified"))
      (node (ref "C27") (pin "2") (pinfunction "2_2") (pintype "unspecified"))
      (node (ref "C28") (pin "2") (pinfunction "2_2") (pintype "unspecified"))
      (node (ref "C29") (pin "2") (pinfunction "2_2") (pintype "unspecified"))
      (node (ref "C30") (pin "2") (pinfunction "2_2") (pintype "unspecified"))
      (node (ref "C31") (pin "2") (pinfunction "2_2") (pintype "unspecified"))
      (node (ref "C32") (pin "2") (pinfunction "2_2") (pintype "unspecified"))
      (node (ref "C33") (pin "2") (pinfunction "2_2") (pintype "unspecified"))
      (node (ref "C34") (pin "2") (pinfunction "2_2") (pintype "unspecified"))
      (node (ref "C35") (pin "2") (pinfunction "2_2") (pintype "unspecified"))
      (node (ref "C36") (pin "2") (pinfunction "2_2") (pintype "unspecified"))
      (node (ref "C37") (pin "2") (pinfunction "2_2") (pintype "unspecified"))
      (node (ref "C38") (pin "2") (pinfunction "2_2") (pintype "unspecified"))
      (node (ref "C39") (pin "2") (pinfunction "2_2") (pintype "unspecified"))
      (node (ref "C40") (pin "2") (pinfunction "2_2") (pintype "unspecified"))
      (node (ref "C41") (pin "2") (pinfunction "2_2") (pintype "unspecified"))
      (node (ref "C42") (pin "2") (pinfunction "2_2") (pintype "unspecified"))
      (node (ref "C43") (pin "2") (pinfunction "2_2") (pintype "unspecified"))
      (node (ref "C44") (pin "2") (pinfunction "2_2") (pintype "unspecified"))
      (node (ref "C51") (pin "2") (pinfunction "2_2") (pintype "unspecified"))
      (node (ref "C52") (pin "2") (pinfunction "2_2") (pintype "unspecified"))
      (node (ref "C53") (pin "2") (pinfunction "2_2") (pintype "unspecified"))
      (node (ref "C54") (pin "2") (pinfunction "2_2") (pintype "unspecified"))
      (node (ref "C55") (pin "2") (pinfunction "2_2") (pintype "unspecified"))
      (node (ref "C56") (pin "2") (pinfunction "2_2") (pintype "unspecified"))
      (node (ref "C57") (pin "2") (pinfunction "2_2") (pintype "unspecified"))
      (node (ref "C58") (pin "2") (pinfunction "2_2") (pintype "unspecified"))
      (node (ref "C59") (pin "2") (pinfunction "2_2") (pintype "unspecified"))
      (node (ref "C6") (pin "2") (pinfunction "2_2") (pintype "unspecified"))
      (node (ref "C60") (pin "2") (pinfunction "2_2") (pintype "unspecified"))
      (node (ref "C61") (pin "2") (pinfunction "2_2") (pintype "unspecified"))
      (node (ref "C62") (pin "2") (pinfunction "2_2") (pintype "unspecified"))
      (node (ref "C63") (pin "2") (pinfunction "2_2") (pintype "unspecified"))
      (node (ref "C64") (pin "2") (pinfunction "2_2") (pintype "unspecified"))
      (node (ref "C65") (pin "2") (pinfunction "2_2") (pintype "unspecified"))
      (node (ref "C66") (pin "2") (pinfunction "2_2") (pintype "unspecified"))
      (node (ref "C67") (pin "2") (pinfunction "2_2") (pintype "unspecified"))
      (node (ref "C68") (pin "2") (pinfunction "2_2") (pintype "unspecified"))
      (node (ref "C69") (pin "2") (pinfunction "2_2") (pintype "unspecified"))
      (node (ref "C70") (pin "2") (pinfunction "2_2") (pintype "unspecified"))
      (node (ref "C71") (pin "2") (pinfunction "2_2") (pintype "unspecified"))
      (node (ref "C72") (pin "2") (pinfunction "2_2") (pintype "unspecified"))
      (node (ref "C73") (pin "2") (pinfunction "2_2") (pintype "unspecified"))
      (node (ref "C74") (pin "2") (pinfunction "2_2") (pintype "unspecified"))
      (node (ref "C75") (pin "2") (pinfunction "2_2") (pintype "unspecified"))
      (node (ref "C76") (pin "2") (pinfunction "2_2") (pintype "unspecified"))
      (node (ref "C77") (pin "2") (pinfunction "2_2") (pintype "unspecified"))
      (node (ref "C78") (pin "2") (pinfunction "2_2") (pintype "unspecified"))
      (node (ref "C79") (pin "2") (pinfunction "2_2") (pintype "unspecified"))
      (node (ref "C80") (pin "2") (pinfunction "2_2") (pintype "unspecified"))
      (node (ref "C81") (pin "2") (pinfunction "2_2") (pintype "unspecified"))
      (node (ref "C82") (pin "2") (pinfunction "2_2") (pintype "unspecified"))
      (node (ref "C83") (pin "2") (pinfunction "2_2") (pintype "unspecified"))
      (node (ref "C84") (pin "2") (pinfunction "2_2") (pintype "unspecified"))
      (node (ref "C85") (pin "2") (pinfunction "2_2") (pintype "unspecified"))
      (node (ref "C9") (pin "2") (pinfunction "2_2") (pintype "unspecified"))
      (node (ref "D2") (pin "1") (pinfunction "K_1") (pintype "unspecified"))
      (node (ref "LED1") (pin "2") (pinfunction "VDD_2") (pintype "unspecified"))
      (node (ref "LED10") (pin "2") (pinfunction "VDD_2") (pintype "unspecified"))
      (node (ref "LED11") (pin "2") (pinfunction "VDD_2") (pintype "unspecified"))
      (node (ref "LED12") (pin "2") (pinfunction "VDD_2") (pintype "unspecified"))
      (node (ref "LED13") (pin "2") (pinfunction "VDD_2") (pintype "unspecified"))
      (node (ref "LED14") (pin "2") (pinfunction "VDD_2") (pintype "unspecified"))
      (node (ref "LED15") (pin "2") (pinfunction "VDD_2") (pintype "unspecified"))
      (node (ref "LED16") (pin "2") (pinfunction "VDD_2") (pintype "unspecified"))
      (node (ref "LED17") (pin "2") (pinfunction "VDD_2") (pintype "unspecified"))
      (node (ref "LED18") (pin "2") (pinfunction "VDD_2") (pintype "unspecified"))
      (node (ref "LED19") (pin "2") (pinfunction "VDD_2") (pintype "unspecified"))
      (node (ref "LED2") (pin "2") (pinfunction "VDD_2") (pintype "unspecified"))
      (node (ref "LED20") (pin "2") (pinfunction "VDD_2") (pintype "unspecified"))
      (node (ref "LED21") (pin "2") (pinfunction "VDD_2") (pintype "unspecified"))
      (node (ref "LED22") (pin "2") (pinfunction "VDD_2") (pintype "unspecified"))
      (node (ref "LED23") (pin "2") (pinfunction "VDD_2") (pintype "unspecified"))
      (node (ref "LED24") (pin "2") (pinfunction "VDD_2") (pintype "unspecified"))
      (node (ref "LED25") (pin "2") (pinfunction "VDD_2") (pintype "unspecified"))
      (node (ref "LED26") (pin "2") (pinfunction "VDD_2") (pintype "unspecified"))
      (node (ref "LED27") (pin "2") (pinfunction "VDD_2") (pintype "unspecified"))
      (node (ref "LED28") (pin "2") (pinfunction "VDD_2") (pintype "unspecified"))
      (node (ref "LED29") (pin "2") (pinfunction "VDD_2") (pintype "unspecified"))
      (node (ref "LED3") (pin "2") (pinfunction "VDD_2") (pintype "unspecified"))
      (node (ref "LED30") (pin "2") (pinfunction "VDD_2") (pintype "unspecified"))
      (node (ref "LED31") (pin "2") (pinfunction "VDD_2") (pintype "unspecified"))
      (node (ref "LED32") (pin "2") (pinfunction "VDD_2") (pintype "unspecified"))
      (node (ref "LED33") (pin "2") (pinfunction "VDD_2") (pintype "unspecified"))
      (node (ref "LED34") (pin "2") (pinfunction "VDD_2") (pintype "unspecified"))
      (node (ref "LED35") (pin "2") (pinfunction "VDD_2") (pintype "unspecified"))
      (node (ref "LED36") (pin "2") (pinfunction "VDD_2") (pintype "unspecified"))
      (node (ref "LED4") (pin "2") (pinfunction "VDD_2") (pintype "unspecified"))
      (node (ref "LED43") (pin "2") (pinfunction "VDD_2") (pintype "unspecified"))
      (node (ref "LED44") (pin "2") (pinfunction "VDD_2") (pintype "unspecified"))
      (node (ref "LED45") (pin "2") (pinfunction "VDD_2") (pintype "unspecified"))
      (node (ref "LED46") (pin "2") (pinfunction "VDD_2") (pintype "unspecified"))
      (node (ref "LED47") (pin "2") (pinfunction "VDD_2") (pintype "unspecified"))
      (node (ref "LED48") (pin "2") (pinfunction "VDD_2") (pintype "unspecified"))
      (node (ref "LED49") (pin "2") (pinfunction "VDD_2") (pintype "unspecified"))
      (node (ref "LED5") (pin "2") (pinfunction "VDD_2") (pintype "unspecified"))
      (node (ref "LED50") (pin "2") (pinfunction "VDD_2") (pintype "unspecified"))
      (node (ref "LED51") (pin "2") (pinfunction "VDD_2") (pintype "unspecified"))
      (node (ref "LED52") (pin "2") (pinfunction "VDD_2") (pintype "unspecified"))
      (node (ref "LED53") (pin "2") (pinfunction "VDD_2") (pintype "unspecified"))
      (node (ref "LED54") (pin "2") (pinfunction "VDD_2") (pintype "unspecified"))
      (node (ref "LED55") (pin "2") (pinfunction "VDD_2") (pintype "unspecified"))
      (node (ref "LED56") (pin "2") (pinfunction "VDD_2") (pintype "unspecified"))
      (node (ref "LED57") (pin "2") (pinfunction "VDD_2") (pintype "unspecified"))
      (node (ref "LED58") (pin "2") (pinfunction "VDD_2") (pintype "unspecified"))
      (node (ref "LED59") (pin "2") (pinfunction "VDD_2") (pintype "unspecified"))
      (node (ref "LED6") (pin "2") (pinfunction "VDD_2") (pintype "unspecified"))
      (node (ref "LED60") (pin "2") (pinfunction "VDD_2") (pintype "unspecified"))
      (node (ref "LED61") (pin "2") (pinfunction "VDD_2") (pintype "unspecified"))
      (node (ref "LED62") (pin "2") (pinfunction "VDD_2") (pintype "unspecified"))
      (node (ref "LED63") (pin "2") (pinfunction "VDD_2") (pintype "unspecified"))
      (node (ref "LED64") (pin "2") (pinfunction "VDD_2") (pintype "unspecified"))
      (node (ref "LED65") (pin "2") (pinfunction "VDD_2") (pintype "unspecified"))
      (node (ref "LED66") (pin "2") (pinfunction "VDD_2") (pintype "unspecified"))
      (node (ref "LED67") (pin "2") (pinfunction "VDD_2") (pintype "unspecified"))
      (node (ref "LED68") (pin "2") (pinfunction "VDD_2") (pintype "unspecified"))
      (node (ref "LED69") (pin "2") (pinfunction "VDD_2") (pintype "unspecified"))
      (node (ref "LED7") (pin "2") (pinfunction "VDD_2") (pintype "unspecified"))
      (node (ref "LED70") (pin "2") (pinfunction "VDD_2") (pintype "unspecified"))
      (node (ref "LED71") (pin "2") (pinfunction "VDD_2") (pintype "unspecified"))
      (node (ref "LED72") (pin "2") (pinfunction "VDD_2") (pintype "unspecified"))
      (node (ref "LED73") (pin "2") (pinfunction "VDD_2") (pintype "unspecified"))
      (node (ref "LED74") (pin "2") (pinfunction "VDD_2") (pintype "unspecified"))
      (node (ref "LED75") (pin "2") (pinfunction "VDD_2") (pintype "unspecified"))
      (node (ref "LED76") (pin "2") (pinfunction "VDD_2") (pintype "unspecified"))
      (node (ref "LED77") (pin "2") (pinfunction "VDD_2") (pintype "unspecified"))
      (node (ref "LED78") (pin "2") (pinfunction "VDD_2") (pintype "unspecified"))
      (node (ref "LED8") (pin "2") (pinfunction "VDD_2") (pintype "unspecified"))
      (node (ref "LED9") (pin "2") (pinfunction "VDD_2") (pintype "unspecified"))
      (node (ref "U2") (pin "23") (pinfunction "5V_23") (pintype "unspecified"))
    )
    (net (code "2") (name "3V3") (class "Default")
      (node (ref "R11") (pin "2") (pinfunction "2_2") (pintype "input"))
      (node (ref "R13") (pin "2") (pinfunction "2_2") (pintype "input"))
      (node (ref "U2") (pin "21") (pinfunction "3V3_21") (pintype "unspecified"))
    )
    (net (code "3") (name "GND") (class "Default")
      (node (ref "C1") (pin "1") (pinfunction "1_1") (pintype "unspecified"))
      (node (ref "C10") (pin "1") (pinfunction "1_1") (pintype "unspecified"))
      (node (ref "C11") (pin "1") (pinfunction "1_1") (pintype "unspecified"))
      (node (ref "C12") (pin "1") (pinfunction "1_1") (pintype "unspecified"))
      (node (ref "C13") (pin "1") (pinfunction "1_1") (pintype "unspecified"))
      (node (ref "C14") (pin "1") (pinfunction "1_1") (pintype "unspecified"))
      (node (ref "C15") (pin "1") (pinfunction "1_1") (pintype "unspecified"))
      (node (ref "C16") (pin "1") (pinfunction "1_1") (pintype "unspecified"))
      (node (ref "C17") (pin "1") (pinfunction "1_1") (pintype "unspecified"))
      (node (ref "C18") (pin "1") (pinfunction "1_1") (pintype "unspecified"))
      (node (ref "C19") (pin "1") (pinfunction "1_1") (pintype "unspecified"))
      (node (ref "C20") (pin "1") (pinfunction "1_1") (pintype "unspecified"))
      (node (ref "C21") (pin "1") (pinfunction "1_1") (pintype "unspecified"))
      (node (ref "C22") (pin "1") (pinfunction "1_1") (pintype "unspecified"))
      (node (ref "C23") (pin "1") (pinfunction "1_1") (pintype "unspecified"))
      (node (ref "C24") (pin "1") (pinfunction "1_1") (pintype "unspecified"))
      (node (ref "C25") (pin "1") (pinfunction "1_1") (pintype "unspecified"))
      (node (ref "C26") (pin "1") (pinfunction "1_1") (pintype "unspecified"))
      (node (ref "C27") (pin "1") (pinfunction "1_1") (pintype "unspecified"))
      (node (ref "C28") (pin "1") (pinfunction "1_1") (pintype "unspecified"))
      (node (ref "C29") (pin "1") (pinfunction "1_1") (pintype "unspecified"))
      (node (ref "C30") (pin "1") (pinfunction "1_1") (pintype "unspecified"))
      (node (ref "C31") (pin "1") (pinfunction "1_1") (pintype "unspecified"))
      (node (ref "C32") (pin "1") (pinfunction "1_1") (pintype "unspecified"))
      (node (ref "C33") (pin "1") (pinfunction "1_1") (pintype "unspecified"))
      (node (ref "C34") (pin "1") (pinfunction "1_1") (pintype "unspecified"))
      (node (ref "C35") (pin "1") (pinfunction "1_1") (pintype "unspecified"))
      (node (ref "C36") (pin "1") (pinfunction "1_1") (pintype "unspecified"))
      (node (ref "C37") (pin "1") (pinfunction "1_1") (pintype "unspecified"))
      (node (ref "C38") (pin "1") (pinfunction "1_1") (pintype "unspecified"))
      (node (ref "C39") (pin "1") (pinfunction "1_1") (pintype "unspecified"))
      (node (ref "C4") (pin "1") (pinfunction "1_1") (pintype "unspecified"))
      (node (ref "C40") (pin "1") (pinfunction "1_1") (pintype "unspecified"))
      (node (ref "C41") (pin "1") (pinfunction "1_1") (pintype "unspecified"))
      (node (ref "C42") (pin "1") (pinfunction "1_1") (pintype "unspecified"))
      (node (ref "C43") (pin "1") (pinfunction "1_1") (pintype "unspecified"))
      (node (ref "C44") (pin "1") (pinfunction "1_1") (pintype "unspecified"))
      (node (ref "C47") (pin "1") (pinfunction "1_1") (pintype "input"))
      (node (ref "C48") (pin "1") (pinfunction "1_1") (pintype "input"))
      (node (ref "C49") (pin "2") (pinfunction "2_2") (pintype "unspecified"))
      (node (ref "C5") (pin "1") (pinfunction "1_1") (pintype "unspecified"))
      (node (ref "C50") (pin "2") (pinfunction "2_2") (pintype "unspecified"))
      (node (ref "C51") (pin "1") (pinfunction "1_1") (pintype "unspecified"))
      (node (ref "C52") (pin "1") (pinfunction "1_1") (pintype "unspecified"))
      (node (ref "C53") (pin "1") (pinfunction "1_1") (pintype "unspecified"))
      (node (ref "C54") (pin "1") (pinfunction "1_1") (pintype "unspecified"))
      (node (ref "C55") (pin "1") (pinfunction "1_1") (pintype "unspecified"))
      (node (ref "C56") (pin "1") (pinfunction "1_1") (pintype "unspecified"))
      (node (ref "C57") (pin "1") (pinfunction "1_1") (pintype "unspecified"))
      (node (ref "C58") (pin "1") (pinfunction "1_1") (pintype "unspecified"))
      (node (ref "C59") (pin "1") (pinfunction "1_1") (pintype "unspecified"))
      (node (ref "C6") (pin "1") (pinfunction "1_1") (pintype "unspecified"))
      (node (ref "C60") (pin "1") (pinfunction "1_1") (pintype "unspecified"))
      (node (ref "C61") (pin "1") (pinfunction "1_1") (pintype "unspecified"))
      (node (ref "C62") (pin "1") (pinfunction "1_1") (pintype "unspecified"))
      (node (ref "C63") (pin "1") (pinfunction "1_1") (pintype "unspecified"))
      (node (ref "C64") (pin "1") (pinfunction "1_1") (pintype "unspecified"))
      (node (ref "C65") (pin "1") (pinfunction "1_1") (pintype "unspecified"))
      (node (ref "C66") (pin "1") (pinfunction "1_1") (pintype "unspecified"))
      (node (ref "C67") (pin "1") (pinfunction "1_1") (pintype "unspecified"))
      (node (ref "C68") (pin "1") (pinfunction "1_1") (pintype "unspecified"))
      (node (ref "C69") (pin "1") (pinfunction "1_1") (pintype "unspecified"))
      (node (ref "C7") (pin "1") (pinfunction "1_1") (pintype "input"))
      (node (ref "C70") (pin "1") (pinfunction "1_1") (pintype "unspecified"))
      (node (ref "C71") (pin "1") (pinfunction "1_1") (pintype "unspecified"))
      (node (ref "C72") (pin "1") (pinfunction "1_1") (pintype "unspecified"))
      (node (ref "C73") (pin "1") (pinfunction "1_1") (pintype "unspecified"))
      (node (ref "C74") (pin "1") (pinfunction "1_1") (pintype "unspecified"))
      (node (ref "C75") (pin "1") (pinfunction "1_1") (pintype "unspecified"))
      (node (ref "C76") (pin "1") (pinfunction "1_1") (pintype "unspecified"))
      (node (ref "C77") (pin "1") (pinfunction "1_1") (pintype "unspecified"))
      (node (ref "C78") (pin "1") (pinfunction "1_1") (pintype "unspecified"))
      (node (ref "C79") (pin "1") (pinfunction "1_1") (pintype "unspecified"))
      (node (ref "C8") (pin "1") (pinfunction "1_1") (pintype "input"))
      (node (ref "C80") (pin "1") (pinfunction "1_1") (pintype "unspecified"))
      (node (ref "C81") (pin "1") (pinfunction "1_1") (pintype "unspecified"))
      (node (ref "C82") (pin "1") (pinfunction "1_1") (pintype "unspecified"))
      (node (ref "C83") (pin "1") (pinfunction "1_1") (pintype "unspecified"))
      (node (ref "C84") (pin "1") (pinfunction "1_1") (pintype "unspecified"))
      (node (ref "C85") (pin "1") (pinfunction "1_1") (pintype "unspecified"))
      (node (ref "C9") (pin "1") (pinfunction "1_1") (pintype "unspecified"))
      (node (ref "LED1") (pin "4") (pinfunction "VSS_4") (pintype "unspecified"))
      (node (ref "LED10") (pin "4") (pinfunction "VSS_4") (pintype "unspecified"))
      (node (ref "LED11") (pin "4") (pinfunction "VSS_4") (pintype "unspecified"))
      (node (ref "LED12") (pin "4") (pinfunction "VSS_4") (pintype "unspecified"))
      (node (ref "LED13") (pin "4") (pinfunction "VSS_4") (pintype "unspecified"))
      (node (ref "LED14") (pin "4") (pinfunction "VSS_4") (pintype "unspecified"))
      (node (ref "LED15") (pin "4") (pinfunction "VSS_4") (pintype "unspecified"))
      (node (ref "LED16") (pin "4") (pinfunction "VSS_4") (pintype "unspecified"))
      (node (ref "LED17") (pin "4") (pinfunction "VSS_4") (pintype "unspecified"))
      (node (ref "LED18") (pin "4") (pinfunction "VSS_4") (pintype "unspecified"))
      (node (ref "LED19") (pin "4") (pinfunction "VSS_4") (pintype "unspecified"))
      (node (ref "LED2") (pin "4") (pinfunction "VSS_4") (pintype "unspecified"))
      (node (ref "LED20") (pin "4") (pinfunction "VSS_4") (pintype "unspecified"))
      (node (ref "LED21") (pin "4") (pinfunction "VSS_4") (pintype "unspecified"))
      (node (ref "LED22") (pin "4") (pinfunction "VSS_4") (pintype "unspecified"))
      (node (ref "LED23") (pin "4") (pinfunction "VSS_4") (pintype "unspecified"))
      (node (ref "LED24") (pin "4") (pinfunction "VSS_4") (pintype "unspecified"))
      (node (ref "LED25") (pin "4") (pinfunction "VSS_4") (pintype "unspecified"))
      (node (ref "LED26") (pin "4") (pinfunction "VSS_4") (pintype "unspecified"))
      (node (ref "LED27") (pin "4") (pinfunction "VSS_4") (pintype "unspecified"))
      (node (ref "LED28") (pin "4") (pinfunction "VSS_4") (pintype "unspecified"))
      (node (ref "LED29") (pin "4") (pinfunction "VSS_4") (pintype "unspecified"))
      (node (ref "LED3") (pin "4") (pinfunction "VSS_4") (pintype "unspecified"))
      (node (ref "LED30") (pin "4") (pinfunction "VSS_4") (pintype "unspecified"))
      (node (ref "LED31") (pin "4") (pinfunction "VSS_4") (pintype "unspecified"))
      (node (ref "LED32") (pin "4") (pinfunction "VSS_4") (pintype "unspecified"))
      (node (ref "LED33") (pin "4") (pinfunction "VSS_4") (pintype "unspecified"))
      (node (ref "LED34") (pin "4") (pinfunction "VSS_4") (pintype "unspecified"))
      (node (ref "LED35") (pin "4") (pinfunction "VSS_4") (pintype "unspecified"))
      (node (ref "LED36") (pin "4") (pinfunction "VSS_4") (pintype "unspecified"))
      (node (ref "LED4") (pin "4") (pinfunction "VSS_4") (pintype "unspecified"))
      (node (ref "LED43") (pin "4") (pinfunction "VSS_4") (pintype "unspecified"))
      (node (ref "LED44") (pin "4") (pinfunction "VSS_4") (pintype "unspecified"))
      (node (ref "LED45") (pin "4") (pinfunction "VSS_4") (pintype "unspecified"))
      (node (ref "LED46") (pin "4") (pinfunction "VSS_4") (pintype "unspecified"))
      (node (ref "LED47") (pin "4") (pinfunction "VSS_4") (pintype "unspecified"))
      (node (ref "LED48") (pin "4") (pinfunction "VSS_4") (pintype "unspecified"))
      (node (ref "LED49") (pin "4") (pinfunction "VSS_4") (pintype "unspecified"))
      (node (ref "LED5") (pin "4") (pinfunction "VSS_4") (pintype "unspecified"))
      (node (ref "LED50") (pin "4") (pinfunction "VSS_4") (pintype "unspecified"))
      (node (ref "LED51") (pin "4") (pinfunction "VSS_4") (pintype "unspecified"))
      (node (ref "LED52") (pin "4") (pinfunction "VSS_4") (pintype "unspecified"))
      (node (ref "LED53") (pin "4") (pinfunction "VSS_4") (pintype "unspecified"))
      (node (ref "LED54") (pin "4") (pinfunction "VSS_4") (pintype "unspecified"))
      (node (ref "LED55") (pin "4") (pinfunction "VSS_4") (pintype "unspecified"))
      (node (ref "LED56") (pin "4") (pinfunction "VSS_4") (pintype "unspecified"))
      (node (ref "LED57") (pin "4") (pinfunction "VSS_4") (pintype "unspecified"))
      (node (ref "LED58") (pin "4") (pinfunction "VSS_4") (pintype "unspecified"))
      (node (ref "LED59") (pin "4") (pinfunction "VSS_4") (pintype "unspecified"))
      (node (ref "LED6") (pin "4") (pinfunction "VSS_4") (pintype "unspecified"))
      (node (ref "LED60") (pin "4") (pinfunction "VSS_4") (pintype "unspecified"))
      (node (ref "LED61") (pin "4") (pinfunction "VSS_4") (pintype "unspecified"))
      (node (ref "LED62") (pin "4") (pinfunction "VSS_4") (pintype "unspecified"))
      (node (ref "LED63") (pin "4") (pinfunction "VSS_4") (pintype "unspecified"))
      (node (ref "LED64") (pin "4") (pinfunction "VSS_4") (pintype "unspecified"))
      (node (ref "LED65") (pin "4") (pinfunction "VSS_4") (pintype "unspecified"))
      (node (ref "LED66") (pin "4") (pinfunction "VSS_4") (pintype "unspecified"))
      (node (ref "LED67") (pin "4") (pinfunction "VSS_4") (pintype "unspecified"))
      (node (ref "LED68") (pin "4") (pinfunction "VSS_4") (pintype "unspecified"))
      (node (ref "LED69") (pin "4") (pinfunction "VSS_4") (pintype "unspecified"))
      (node (ref "LED7") (pin "4") (pinfunction "VSS_4") (pintype "unspecified"))
      (node (ref "LED70") (pin "4") (pinfunction "VSS_4") (pintype "unspecified"))
      (node (ref "LED71") (pin "4") (pinfunction "VSS_4") (pintype "unspecified"))
      (node (ref "LED72") (pin "4") (pinfunction "VSS_4") (pintype "unspecified"))
      (node (ref "LED73") (pin "4") (pinfunction "VSS_4") (pintype "unspecified"))
      (node (ref "LED74") (pin "4") (pinfunction "VSS_4") (pintype "unspecified"))
      (node (ref "LED75") (pin "4") (pinfunction "VSS_4") (pintype "unspecified"))
      (node (ref "LED76") (pin "4") (pinfunction "VSS_4") (pintype "unspecified"))
      (node (ref "LED77") (pin "4") (pinfunction "VSS_4") (pintype "unspecified"))
      (node (ref "LED78") (pin "4") (pinfunction "VSS_4") (pintype "unspecified"))
      (node (ref "LED8") (pin "4") (pinfunction "VSS_4") (pintype "unspecified"))
      (node (ref "LED9") (pin "4") (pinfunction "VSS_4") (pintype "unspecified"))
      (node (ref "P1") (pin "1") (pinfunction "1_1") (pintype "unspecified"))
      (node (ref "P4") (pin "1") (pinfunction "1_1") (pintype "unspecified"))
      (node (ref "P5") (pin "1") (pinfunction "1_1") (pintype "unspecified"))
      (node (ref "R10") (pin "1") (pinfunction "1_1") (pintype "input"))
      (node (ref "R12") (pin "1") (pinfunction "1_1") (pintype "input"))
      (node (ref "R14") (pin "1") (pinfunction "1_1") (pintype "input"))
      (node (ref "R2") (pin "1") (pinfunction "1_1") (pintype "input"))
      (node (ref "R9") (pin "1") (pinfunction "1_1") (pintype "input"))
      (node (ref "SW1") (pin "3") (pinfunction "3_3") (pintype "unspecified"))
      (node (ref "SW1") (pin "4") (pinfunction "4_4") (pintype "unspecified"))
      (node (ref "U1") (pin "1") (pinfunction "GND_1") (pintype "unspecified"))
      (node (ref "U2") (pin "22") (pinfunction "GND_22") (pintype "unspecified"))
    )
    (net (code "4") (name "LEFT") (class "Default")
      (node (ref "LED1") (pin "1") (pinfunction "DIN_1") (pintype "unspecified"))
      (node (ref "U2") (pin "15") (pinfunction "GP14_15") (pintype "unspecified"))
    )
    (net (code "5") (name "Net-(C45-Pad1)") (class "Default")
      (node (ref "C45") (pin "1") (pinfunction "1_1") (pintype "input"))
      (node (ref "P2") (pin "2") (pinfunction "2_2") (pintype "unspecified"))
      (node (ref "R3") (pin "2") (pinfunction "2_2") (pintype "input"))
    )
    (net (code "6") (name "Net-(C45-Pad2)") (class "Default")
      (node (ref "C45") (pin "2") (pinfunction "2_2") (pintype "input"))
      (node (ref "C49") (pin "1") (pinfunction "1_1") (pintype "unspecified"))
      (node (ref "R5") (pin "1") (pinfunction "1_1") (pintype "input"))
    )
    (net (code "7") (name "Net-(C46-Pad1)") (class "Default")
      (node (ref "C46") (pin "1") (pinfunction "1_1") (pintype "input"))
      (node (ref "P3") (pin "1") (pinfunction "1_1") (pintype "unspecified"))
      (node (ref "R4") (pin "2") (pinfunction "2_2") (pintype "input"))
    )
    (net (code "8") (name "Net-(C46-Pad2)") (class "Default")
      (node (ref "C46") (pin "2") (pinfunction "2_2") (pintype "input"))
      (node (ref "C50") (pin "1") (pinfunction "1_1") (pintype "unspecified"))
      (node (ref "R6") (pin "1") (pinfunction "1_1") (pintype "input"))
    )
    (net (code "9") (name "Net-(D1-A)") (class "Default")
      (node (ref "D1") (pin "2") (pinfunction "A_2") (pintype "unspecified"))
      (node (ref "P1") (pin "2") (pinfunction "2_2") (pintype "unspecified"))
    )
    (net (code "10") (name "Net-(D1-K)") (class "Default")
      (node (ref "C1") (pin "2") (pinfunction "2_2") (pintype "unspecified"))
      (node (ref "D1") (pin "1") (pinfunction "K_1") (pintype "unspecified"))
      (node (ref "U1") (pin "3") (pinfunction "VIN_3") (pintype "unspecified"))
    )
    (net (code "11") (name "Net-(D2-A)") (class "Default")
      (node (ref "C3") (pin "2") (pinfunction "2_2") (pintype "unspecified"))
      (node (ref "C4") (pin "2") (pinfunction "2_2") (pintype "unspecified"))
      (node (ref "C5") (pin "2") (pinfunction "2_2") (pintype "unspecified"))
      (node (ref "D2") (pin "2") (pinfunction "A_2") (pintype "unspecified"))
      (node (ref "L1") (pin "2") (pinfunction "2_2") (pintype "unspecified"))
      (node (ref "R1") (pin "2") (pinfunction "2_2") (pintype "input"))
    )
    (net (code "12") (name "Net-(LED1-DOUT)") (class "Default")
      (node (ref "LED1") (pin "3") (pinfunction "DOUT_3") (pintype "unspecified"))
      (node (ref "LED2") (pin "1") (pinfunction "DIN_1") (pintype "unspecified"))
    )
    (net (code "13") (name "Net-(LED2-DOUT)") (class "Default")
      (node (ref "LED2") (pin "3") (pinfunction "DOUT_3") (pintype "unspecified"))
      (node (ref "LED3") (pin "1") (pinfunction "DIN_1") (pintype "unspecified"))
    )
    (net (code "14") (name "Net-(LED3-DOUT)") (class "Default")
      (node (ref "LED3") (pin "3") (pinfunction "DOUT_3") (pintype "unspecified"))
      (node (ref "LED4") (pin "1") (pinfunction "DIN_1") (pintype "unspecified"))
    )
    (net (code "15") (name "Net-(LED4-DOUT)") (class "Default")
      (node (ref "LED4") (pin "3") (pinfunction "DOUT_3") (pintype "unspecified"))
      (node (ref "LED5") (pin "1") (pinfunction "DIN_1") (pintype "unspecified"))
    )
    (net (code "16") (name "Net-(LED5-DOUT)") (class "Default")
      (node (ref "LED5") (pin "3") (pinfunction "DOUT_3") (pintype "unspecified"))
      (node (ref "LED6") (pin "1") (pinfunction "DIN_1") (pintype "unspecified"))
    )
    (net (code "17") (name "Net-(LED6-DOUT)") (class "Default")
      (node (ref "LED6") (pin "3") (pinfunction "DOUT_3") (pintype "unspecified"))
      (node (ref "LED7") (pin "1") (pinfunction "DIN_1") (pintype "unspecified"))
    )
    (net (code "18") (name "Net-(LED7-DOUT)") (class "Default")
      (node (ref "LED7") (pin "3") (pinfunction "DOUT_3") (pintype "unspecified"))
      (node (ref "LED8") (pin "1") (pinfunction "DIN_1") (pintype "unspecified"))
    )
    (net (code "19") (name "Net-(LED8-DOUT)") (class "Default")
      (node (ref "LED8") (pin "3") (pinfunction "DOUT_3") (pintype "unspecified"))
      (node (ref "LED9") (pin "1") (pinfunction "DIN_1") (pintype "unspecified"))
    )
    (net (code "20") (name "Net-(LED10-DIN)") (class "Default")
      (node (ref "LED10") (pin "1") (pinfunction "DIN_1") (pintype "unspecified"))
      (node (ref "LED9") (pin "3") (pinfunction "DOUT_3") (pintype "unspecified"))
    )
    (net (code "21") (name "Net-(LED10-DOUT)") (class "Default")
      (node (ref "LED10") (pin "3") (pinfunction "DOUT_3") (pintype "unspecified"))
      (node (ref "LED11") (pin "1") (pinfunction "DIN_1") (pintype "unspecified"))
    )
    (net (code "22") (name "Net-(LED11-DOUT)") (class "Default")
      (node (ref "LED11") (pin "3") (pinfunction "DOUT_3") (pintype "unspecified"))
      (node (ref "LED12") (pin "1") (pinfunction "DIN_1") (pintype "unspecified"))
    )
    (net (code "23") (name "Net-(LED12-DOUT)") (class "Default")
      (node (ref "LED12") (pin "3") (pinfunction "DOUT_3") (pintype "unspecified"))
      (node (ref "LED13") (pin "1") (pinfunction "DIN_1") (pintype "unspecified"))
    )
    (net (code "24") (name "Net-(LED13-DOUT)") (class "Default")
      (node (ref "LED13") (pin "3") (pinfunction "DOUT_3") (pintype "unspecified"))
      (node (ref "LED14") (pin "1") (pinfunction "DIN_1") (pintype "unspecified"))
    )
    (net (code "25") (name "Net-(LED14-DOUT)") (class "Default")
      (node (ref "LED14") (pin "3") (pinfunction "DOUT_3") (pintype "unspecified"))
      (node (ref "LED15") (pin "1") (pinfunction "DIN_1") (pintype "unspecified"))
    )
    (net (code "26") (name "Net-(LED15-DOUT)") (class "Default")
      (node (ref "LED15") (pin "3") (pinfunction "DOUT_3") (pintype "unspecified"))
      (node (ref "LED16") (pin "1") (pinfunction "DIN_1") (pintype "unspecified"))
    )
    (net (code "27") (name "Net-(LED16-DOUT)") (class "Default")
      (node (ref "LED16") (pin "3") (pinfunction "DOUT_3") (pintype "unspecified"))
      (node (ref "LED17") (pin "1") (pinfunction "DIN_1") (pintype "unspecified"))
    )
    (net (code "28") (name "Net-(LED17-DOUT)") (class "Default")
      (node (ref "LED17") (pin "3") (pinfunction "DOUT_3") (pintype "unspecified"))
      (node (ref "LED18") (pin "1") (pinfunction "DIN_1") (pintype "unspecified"))
    )
    (net (code "29") (name "Net-(LED18-DOUT)") (class "Default")
      (node (ref "LED18") (pin "3") (pinfunction "DOUT_3") (pintype "unspecified"))
      (node (ref "LED19") (pin "1") (pinfunction "DIN_1") (pintype "unspecified"))
    )
    (net (code "30") (name "Net-(LED19-DOUT)") (class "Default")
      (node (ref "LED19") (pin "3") (pinfunction "DOUT_3") (pintype "unspecified"))
      (node (ref "LED20") (pin "1") (pinfunction "DIN_1") (pintype "unspecified"))
    )
    (net (code "31") (name "Net-(LED20-DOUT)") (class "Default")
      (node (ref "LED20") (pin "3") (pinfunction "DOUT_3") (pintype "unspecified"))
      (node (ref "LED21") (pin "1") (pinfunction "DIN_1") (pintype "unspecified"))
    )
    (net (code "32") (name "Net-(LED21-DOUT)") (class "Default")
      (node (ref "LED21") (pin "3") (pinfunction "DOUT_3") (pintype "unspecified"))
      (node (ref "LED22") (pin "1") (pinfunction "DIN_1") (pintype "unspecified"))
    )
    (net (code "33") (name "Net-(LED22-DOUT)") (class "Default")
      (node (ref "LED22") (pin "3") (pinfunction "DOUT_3") (pintype "unspecified"))
      (node (ref "LED23") (pin "1") (pinfunction "DIN_1") (pintype "unspecified"))
    )
    (net (code "34") (name "Net-(LED23-DOUT)") (class "Default")
      (node (ref "LED23") (pin "3") (pinfunction "DOUT_3") (pintype "unspecified"))
      (node (ref "LED24") (pin "1") (pinfunction "DIN_1") (pintype "unspecified"))
    )
    (net (code "35") (name "Net-(LED24-DOUT)") (class "Default")
      (node (ref "LED24") (pin "3") (pinfunction "DOUT_3") (pintype "unspecified"))
      (node (ref "LED25") (pin "1") (pinfunction "DIN_1") (pintype "unspecified"))
    )
    (net (code "36") (name "Net-(LED25-DOUT)") (class "Default")
      (node (ref "LED25") (pin "3") (pinfunction "DOUT_3") (pintype "unspecified"))
      (node (ref "LED26") (pin "1") (pinfunction "DIN_1") (pintype "unspecified"))
    )
    (net (code "37") (name "Net-(LED26-DOUT)") (class "Default")
      (node (ref "LED26") (pin "3") (pinfunction "DOUT_3") (pintype "unspecified"))
      (node (ref "LED27") (pin "1") (pinfunction "DIN_1") (pintype "unspecified"))
    )
    (net (code "38") (name "Net-(LED27-DOUT)") (class "Default")
      (node (ref "LED27") (pin "3") (pinfunction "DOUT_3") (pintype "unspecified"))
      (node (ref "LED28") (pin "1") (pinfunction "DIN_1") (pintype "unspecified"))
    )
    (net (code "39") (name "Net-(LED28-DOUT)") (class "Default")
      (node (ref "LED28") (pin "3") (pinfunction "DOUT_3") (pintype "unspecified"))
      (node (ref "LED29") (pin "1") (pinfunction "DIN_1") (pintype "unspecified"))
    )
    (net (code "40") (name "Net-(LED29-DOUT)") (class "Default")
      (node (ref "LED29") (pin "3") (pinfunction "DOUT_3") (pintype "unspecified"))
      (node (ref "LED30") (pin "1") (pinfunction "DIN_1") (pintype "unspecified"))
    )
    (net (code "41") (name "Net-(LED30-DOUT)") (class "Default")
      (node (ref "LED30") (pin "3") (pinfunction "DOUT_3") (pintype "unspecified"))
      (node (ref "LED31") (pin "1") (pinfunction "DIN_1") (pintype "unspecified"))
    )
    (net (code "42") (name "Net-(LED31-DOUT)") (class "Default")
      (node (ref "LED31") (pin "3") (pinfunction "DOUT_3") (pintype "unspecified"))
      (node (ref "LED32") (pin "1") (pinfunction "DIN_1") (pintype "unspecified"))
    )
    (net (code "43") (name "Net-(LED32-DOUT)") (class "Default")
      (node (ref "LED32") (pin "3") (pinfunction "DOUT_3") (pintype "unspecified"))
      (node (ref "LED33") (pin "1") (pinfunction "DIN_1") (pintype "unspecified"))
    )
    (net (code "44") (name "Net-(LED33-DOUT)") (class "Default")
      (node (ref "LED33") (pin "3") (pinfunction "DOUT_3") (pintype "unspecified"))
      (node (ref "LED34") (pin "1") (pinfunction "DIN_1") (pintype "unspecified"))
    )
    (net (code "45") (name "Net-(LED34-DOUT)") (class "Default")
      (node (ref "LED34") (pin "3") (pinfunction "DOUT_3") (pintype "unspecified"))
      (node (ref "LED35") (pin "1") (pinfunction "DIN_1") (pintype "unspecified"))
    )
    (net (code "46") (name "Net-(LED35-DOUT)") (class "Default")
      (node (ref "LED35") (pin "3") (pinfunction "DOUT_3") (pintype "unspecified"))
      (node (ref "LED36") (pin "1") (pinfunction "DIN_1") (pintype "unspecified"))
    )
    (net (code "47") (name "Net-(LED43-DOUT)") (class "Default")
      (node (ref "LED43") (pin "3") (pinfunction "DOUT_3") (pintype "unspecified"))
      (node (ref "LED44") (pin "1") (pinfunction "DIN_1") (pintype "unspecified"))
    )
    (net (code "48") (name "Net-(LED44-DOUT)") (class "Default")
      (node (ref "LED44") (pin "3") (pinfunction "DOUT_3") (pintype "unspecified"))
      (node (ref "LED45") (pin "1") (pinfunction "DIN_1") (pintype "unspecified"))
    )
    (net (code "49") (name "Net-(LED45-DOUT)") (class "Default")
      (node (ref "LED45") (pin "3") (pinfunction "DOUT_3") (pintype "unspecified"))
      (node (ref "LED46") (pin "1") (pinfunction "DIN_1") (pintype "unspecified"))
    )
    (net (code "50") (name "Net-(LED46-DOUT)") (class "Default")
      (node (ref "LED46") (pin "3") (pinfunction "DOUT_3") (pintype "unspecified"))
      (node (ref "LED47") (pin "1") (pinfunction "DIN_1") (pintype "unspecified"))
    )
    (net (code "51") (name "Net-(LED47-DOUT)") (class "Default")
      (node (ref "LED47") (pin "3") (pinfunction "DOUT_3") (pintype "unspecified"))
      (node (ref "LED48") (pin "1") (pinfunction "DIN_1") (pintype "unspecified"))
    )
    (net (code "52") (name "Net-(LED48-DOUT)") (class "Default")
      (node (ref "LED48") (pin "3") (pinfunction "DOUT_3") (pintype "unspecified"))
      (node (ref "LED49") (pin "1") (pinfunction "DIN_1") (pintype "unspecified"))
    )
    (net (code "53") (name "Net-(LED49-DOUT)") (class "Default")
      (node (ref "LED49") (pin "3") (pinfunction "DOUT_3") (pintype "unspecified"))
      (node (ref "LED50") (pin "1") (pinfunction "DIN_1") (pintype "unspecified"))
    )
    (net (code "54") (name "Net-(LED50-DOUT)") (class "Default")
      (node (ref "LED50") (pin "3") (pinfunction "DOUT_3") (pintype "unspecified"))
      (node (ref "LED51") (pin "1") (pinfunction "DIN_1") (pintype "unspecified"))
    )
    (net (code "55") (name "Net-(LED51-DOUT)") (class "Default")
      (node (ref "LED51") (pin "3") (pinfunction "DOUT_3") (pintype "unspecified"))
      (node (ref "LED52") (pin "1") (pinfunction "DIN_1") (pintype "unspecified"))
    )
    (net (code "56") (name "Net-(LED52-DOUT)") (class "Default")
      (node (ref "LED52") (pin "3") (pinfunction "DOUT_3") (pintype "unspecified"))
      (node (ref "LED53") (pin "1") (pinfunction "DIN_1") (pintype "unspecified"))
    )
    (net (code "57") (name "Net-(LED53-DOUT)") (class "Default")
      (node (ref "LED53") (pin "3") (pinfunction "DOUT_3") (pintype "unspecified"))
      (node (ref "LED54") (pin "1") (pinfunction "DIN_1") (pintype "unspecified"))
    )
    (net (code "58") (name "Net-(LED54-DOUT)") (class "Default")
      (node (ref "LED54") (pin "3") (pinfunction "DOUT_3") (pintype "unspecified"))
      (node (ref "LED55") (pin "1") (pinfunction "DIN_1") (pintype "unspecified"))
    )
    (net (code "59") (name "Net-(LED55-DOUT)") (class "Default")
      (node (ref "LED55") (pin "3") (pinfunction "DOUT_3") (pintype "unspecified"))
      (node (ref "LED56") (pin "1") (pinfunction "DIN_1") (pintype "unspecified"))
    )
    (net (code "60") (name "Net-(LED56-DOUT)") (class "Default")
      (node (ref "LED56") (pin "3") (pinfunction "DOUT_3") (pintype "unspecified"))
      (node (ref "LED57") (pin "1") (pinfunction "DIN_1") (pintype "unspecified"))
    )
    (net (code "61") (name "Net-(LED57-DOUT)") (class "Default")
      (node (ref "LED57") (pin "3") (pinfunction "DOUT_3") (pintype "unspecified"))
      (node (ref "LED58") (pin "1") (pinfunction "DIN_1") (pintype "unspecified"))
    )
    (net (code "62") (name "Net-(LED58-DOUT)") (class "Default")
      (node (ref "LED58") (pin "3") (pinfunction "DOUT_3") (pintype "unspecified"))
      (node (ref "LED59") (pin "1") (pinfunction "DIN_1") (pintype "unspecified"))
    )
    (net (code "63") (name "Net-(LED59-DOUT)") (class "Default")
      (node (ref "LED59") (pin "3") (pinfunction "DOUT_3") (pintype "unspecified"))
      (node (ref "LED60") (pin "1") (pinfunction "DIN_1") (pintype "unspecified"))
    )
    (net (code "64") (name "Net-(LED60-DOUT)") (class "Default")
      (node (ref "LED60") (pin "3") (pinfunction "DOUT_3") (pintype "unspecified"))
      (node (ref "LED61") (pin "1") (pinfunction "DIN_1") (pintype "unspecified"))
    )
    (net (code "65") (name "Net-(LED61-DOUT)") (class "Default")
      (node (ref "LED61") (pin "3") (pinfunction "DOUT_3") (pintype "unspecified"))
      (node (ref "LED62") (pin "1") (pinfunction "DIN_1") (pintype "unspecified"))
    )
    (net (code "66") (name "Net-(LED62-DOUT)") (class "Default")
      (node (ref "LED62") (pin "3") (pinfunction "DOUT_3") (pintype "unspecified"))
      (node (ref "LED63") (pin "1") (pinfunction "DIN_1") (pintype "unspecified"))
    )
    (net (code "67") (name "Net-(LED63-DOUT)") (class "Default")
      (node (ref "LED63") (pin "3") (pinfunction "DOUT_3") (pintype "unspecified"))
      (node (ref "LED64") (pin "1") (pinfunction "DIN_1") (pintype "unspecified"))
    )
    (net (code "68") (name "Net-(LED64-DOUT)") (class "Default")
      (node (ref "LED64") (pin "3") (pinfunction "DOUT_3") (pintype "unspecified"))
      (node (ref "LED65") (pin "1") (pinfunction "DIN_1") (pintype "unspecified"))
    )
    (net (code "69") (name "Net-(LED65-DOUT)") (class "Default")
      (node (ref "LED65") (pin "3") (pinfunction "DOUT_3") (pintype "unspecified"))
      (node (ref "LED66") (pin "1") (pinfunction "DIN_1") (pintype "unspecified"))
    )
    (net (code "70") (name "Net-(LED66-DOUT)") (class "Default")
      (node (ref "LED66") (pin "3") (pinfunction "DOUT_3") (pintype "unspecified"))
      (node (ref "LED67") (pin "1") (pinfunction "DIN_1") (pintype "unspecified"))
    )
    (net (code "71") (name "Net-(LED67-DOUT)") (class "Default")
      (node (ref "LED67") (pin "3") (pinfunction "DOUT_3") (pintype "unspecified"))
      (node (ref "LED68") (pin "1") (pinfunction "DIN_1") (pintype "unspecified"))
    )
    (net (code "72") (name "Net-(LED68-DOUT)") (class "Default")
      (node (ref "LED68") (pin "3") (pinfunction "DOUT_3") (pintype "unspecified"))
      (node (ref "LED69") (pin "1") (pinfunction "DIN_1") (pintype "unspecified"))
    )
    (net (code "73") (name "Net-(LED69-DOUT)") (class "Default")
      (node (ref "LED69") (pin "3") (pinfunction "DOUT_3") (pintype "unspecified"))
      (node (ref "LED70") (pin "1") (pinfunction "DIN_1") (pintype "unspecified"))
    )
    (net (code "74") (name "Net-(LED70-DOUT)") (class "Default")
      (node (ref "LED70") (pin "3") (pinfunction "DOUT_3") (pintype "unspecified"))
      (node (ref "LED71") (pin "1") (pinfunction "DIN_1") (pintype "unspecified"))
    )
    (net (code "75") (name "Net-(LED71-DOUT)") (class "Default")
      (node (ref "LED71") (pin "3") (pinfunction "DOUT_3") (pintype "unspecified"))
      (node (ref "LED72") (pin "1") (pinfunction "DIN_1") (pintype "unspecified"))
    )
    (net (code "76") (name "Net-(LED72-DOUT)") (class "Default")
      (node (ref "LED72") (pin "3") (pinfunction "DOUT_3") (pintype "unspecified"))
      (node (ref "LED73") (pin "1") (pinfunction "DIN_1") (pintype "unspecified"))
    )
    (net (code "77") (name "Net-(LED73-DOUT)") (class "Default")
      (node (ref "LED73") (pin "3") (pinfunction "DOUT_3") (pintype "unspecified"))
      (node (ref "LED74") (pin "1") (pinfunction "DIN_1") (pintype "unspecified"))
    )
    (net (code "78") (name "Net-(LED74-DOUT)") (class "Default")
      (node (ref "LED74") (pin "3") (pinfunction "DOUT_3") (pintype "unspecified"))
      (node (ref "LED75") (pin "1") (pinfunction "DIN_1") (pintype "unspecified"))
    )
    (net (code "79") (name "Net-(LED75-DOUT)") (class "Default")
      (node (ref "LED75") (pin "3") (pinfunction "DOUT_3") (pintype "unspecified"))
      (node (ref "LED76") (pin "1") (pinfunction "DIN_1") (pintype "unspecified"))
    )
    (net (code "80") (name "Net-(LED76-DOUT)") (class "Default")
      (node (ref "LED76") (pin "3") (pinfunction "DOUT_3") (pintype "unspecified"))
      (node (ref "LED77") (pin "1") (pinfunction "DIN_1") (pintype "unspecified"))
    )
    (net (code "81") (name "Net-(LED77-DOUT)") (class "Default")
      (node (ref "LED77") (pin "3") (pinfunction "DOUT_3") (pintype "unspecified"))
      (node (ref "LED78") (pin "1") (pinfunction "DIN_1") (pintype "unspecified"))
    )
    (net (code "82") (name "Net-(P2-Pad1)") (class "Default")
      (node (ref "P2") (pin "1") (pinfunction "1_1") (pintype "unspecified"))
      (node (ref "R3") (pin "1") (pinfunction "1_1") (pintype "input"))
    )
    (net (code "83") (name "Net-(P3-Pad2)") (class "Default")
      (node (ref "P3") (pin "2") (pinfunction "2_2") (pintype "unspecified"))
      (node (ref "R4") (pin "1") (pinfunction "1_1") (pintype "input"))
    )
    (net (code "84") (name "Net-(P4-Pad2)") (class "Default")
      (node (ref "P4") (pin "2") (pinfunction "2_2") (pintype "unspecified"))
      (node (ref "R7") (pin "2") (pinfunction "2_2") (pintype "input"))
    )
    (net (code "85") (name "Net-(P5-Pad2)") (class "Default")
      (node (ref "P5") (pin "2") (pinfunction "2_2") (pintype "unspecified"))
      (node (ref "R8") (pin "2") (pinfunction "2_2") (pintype "input"))
    )
    (net (code "86") (name "Net-(U1-BOOT)") (class "Default")
      (node (ref "C2") (pin "1") (pinfunction "1_1") (pintype "unspecified"))
      (node (ref "U1") (pin "6") (pinfunction "BOOT_6") (pintype "unspecified"))
    )
    (net (code "87") (name "Net-(U1-FB)") (class "Default")
      (node (ref "C3") (pin "1") (pinfunction "1_1") (pintype "unspecified"))
      (node (ref "R1") (pin "1") (pinfunction "1_1") (pintype "input"))
      (node (ref "R2") (pin "2") (pinfunction "2_2") (pintype "input"))
      (node (ref "U1") (pin "4") (pinfunction "FB_4") (pintype "unspecified"))
    )
    (net (code "88") (name "Net-(U1-SW)") (class "Default")
      (node (ref "C2") (pin "2") (pinfunction "2_2") (pintype "unspecified"))
      (node (ref "L1") (pin "1") (pinfunction "1_1") (pintype "unspecified"))
      (node (ref "U1") (pin "2") (pinfunction "SW_2") (pintype "unspecified"))
    )
    (net (code "89") (name "Net-(U2-GP2)") (class "Default")
      (node (ref "C47") (pin "2") (pinfunction "2_2") (pintype "input"))
      (node (ref "R7") (pin "1") (pinfunction "1_1") (pintype "input"))
      (node (ref "R9") (pin "2") (pinfunction "2_2") (pintype "input"))
      (node (ref "U2") (pin "3") (pinfunction "GP2_3") (pintype "unspecified"))
    )
    (net (code "90") (name "Net-(U2-GP3)") (class "Default")
      (node (ref "C48") (pin "2") (pinfunction "2_2") (pintype "input"))
      (node (ref "R10") (pin "2") (pinfunction "2_2") (pintype "input"))
      (node (ref "R8") (pin "1") (pinfunction "1_1") (pintype "input"))
      (node (ref "U2") (pin "4") (pinfunction "GP3_4") (pintype "unspecified"))
    )
    (net (code "91") (name "Net-(U2-GP8)") (class "Default")
      (node (ref "SW1") (pin "1") (pinfunction "1_1") (pintype "unspecified"))
      (node (ref "SW1") (pin "2") (pinfunction "2_2") (pintype "unspecified"))
      (node (ref "U2") (pin "9") (pinfunction "GP8_9") (pintype "unspecified"))
    )
    (net (code "92") (name "Net-(U2-GP27)") (class "Default")
      (node (ref "C7") (pin "2") (pinfunction "2_2") (pintype "input"))
      (node (ref "R13") (pin "1") (pinfunction "1_1") (pintype "input"))
      (node (ref "R14") (pin "2") (pinfunction "2_2") (pintype "input"))
      (node (ref "R6") (pin "2") (pinfunction "2_2") (pintype "input"))
      (node (ref "U2") (pin "18") (pinfunction "GP27_18") (pintype "unspecified"))
    )
    (net (code "93") (name "Net-(U2-GP28)") (class "Default")
      (node (ref "C8") (pin "2") (pinfunction "2_2") (pintype "input"))
      (node (ref "R11") (pin "1") (pinfunction "1_1") (pintype "input"))
      (node (ref "R12") (pin "2") (pinfunction "2_2") (pintype "input"))
      (node (ref "R5") (pin "2") (pinfunction "2_2") (pintype "input"))
      (node (ref "U2") (pin "19") (pinfunction "GP28_19") (pintype "unspecified"))
    )
    (net (code "94") (name "RIGHT") (class "Default")
      (node (ref "LED43") (pin "1") (pinfunction "DIN_1") (pintype "unspecified"))
      (node (ref "U2") (pin "16") (pinfunction "GP15_16") (pintype "unspecified"))
    )
    (net (code "95") (name "unconnected-(LED36-DOUT-Pad3)") (class "Default")
      (node (ref "LED36") (pin "3") (pinfunction "DOUT_3") (pintype "unspecified+no_connect"))
    )
    (net (code "96") (name "unconnected-(LED78-DOUT-Pad3)") (class "Default")
      (node (ref "LED78") (pin "3") (pinfunction "DOUT_3") (pintype "unspecified+no_connect"))
    )
    (net (code "97") (name "unconnected-(U1-EN-Pad5)") (class "Default")
      (node (ref "U1") (pin "5") (pinfunction "EN_5") (pintype "unspecified+no_connect"))
    )
    (net (code "98") (name "unconnected-(U2-GP0-Pad1)") (class "Default")
      (node (ref "U2") (pin "1") (pinfunction "GP0_1") (pintype "unspecified+no_connect"))
    )
    (net (code "99") (name "unconnected-(U2-GP1-Pad2)") (class "Default")
      (node (ref "U2") (pin "2") (pinfunction "GP1_2") (pintype "unspecified+no_connect"))
    )
    (net (code "100") (name "unconnected-(U2-GP4-Pad5)") (class "Default")
      (node (ref "U2") (pin "5") (pinfunction "GP4_5") (pintype "unspecified+no_connect"))
    )
    (net (code "101") (name "unconnected-(U2-GP5-Pad6)") (class "Default")
      (node (ref "U2") (pin "6") (pinfunction "GP5_6") (pintype "unspecified+no_connect"))
    )
    (net (code "102") (name "unconnected-(U2-GP6-Pad7)") (class "Default")
      (node (ref "U2") (pin "7") (pinfunction "GP6_7") (pintype "unspecified+no_connect"))
    )
    (net (code "103") (name "unconnected-(U2-GP7-Pad8)") (class "Default")
      (node (ref "U2") (pin "8") (pinfunction "GP7_8") (pintype "unspecified+no_connect"))
    )
    (net (code "104") (name "unconnected-(U2-GP9-Pad10)") (class "Default")
      (node (ref "U2") (pin "10") (pinfunction "GP9_10") (pintype "unspecified+no_connect"))
    )
    (net (code "105") (name "unconnected-(U2-GP10-Pad11)") (class "Default")
      (node (ref "U2") (pin "11") (pinfunction "GP10_11") (pintype "unspecified+no_connect"))
    )
    (net (code "106") (name "unconnected-(U2-GP11-Pad12)") (class "Default")
      (node (ref "U2") (pin "12") (pinfunction "GP11_12") (pintype "unspecified+no_connect"))
    )
    (net (code "107") (name "unconnected-(U2-GP12-Pad13)") (class "Default")
      (node (ref "U2") (pin "13") (pinfunction "GP12_13") (pintype "unspecified+no_connect"))
    )
    (net (code "108") (name "unconnected-(U2-GP13-Pad14)") (class "Default")
      (node (ref "U2") (pin "14") (pinfunction "GP13_14") (pintype "unspecified+no_connect"))
    )
    (net (code "109") (name "unconnected-(U2-GP26-Pad17)") (class "Default")
      (node (ref "U2") (pin "17") (pinfunction "GP26_17") (pintype "unspecified+no_connect"))
    )
    (net (code "110") (name "unconnected-(U2-GP29-Pad20)") (class "Default")
      (node (ref "U2") (pin "20") (pinfunction "GP29_20") (pintype "unspecified+no_connect"))
    )
  )
)
